# PRN_S2_v1_0.net
KiCad netlist of a schematic drawn in EAGLE
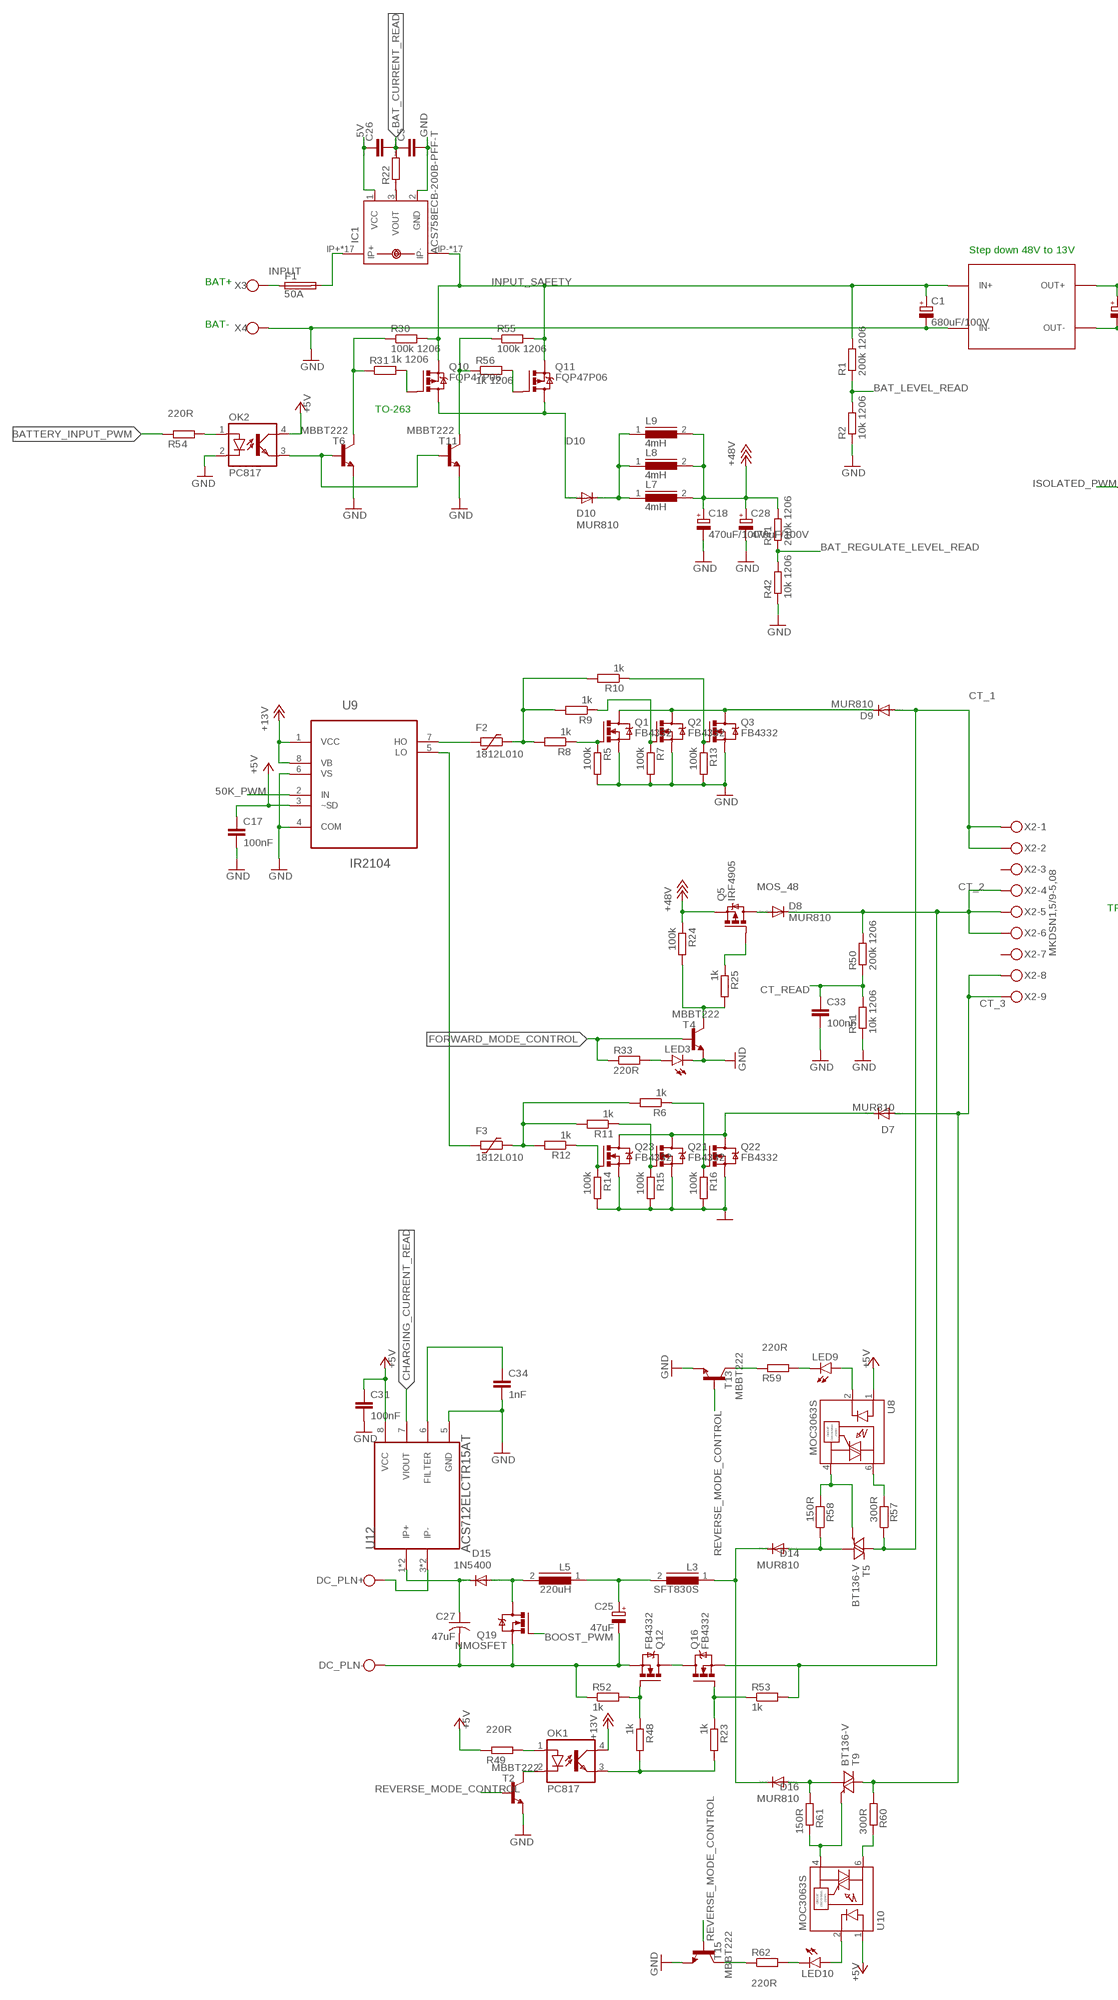
[diagram p0: schematic, sheet 1, part 1 of 2]
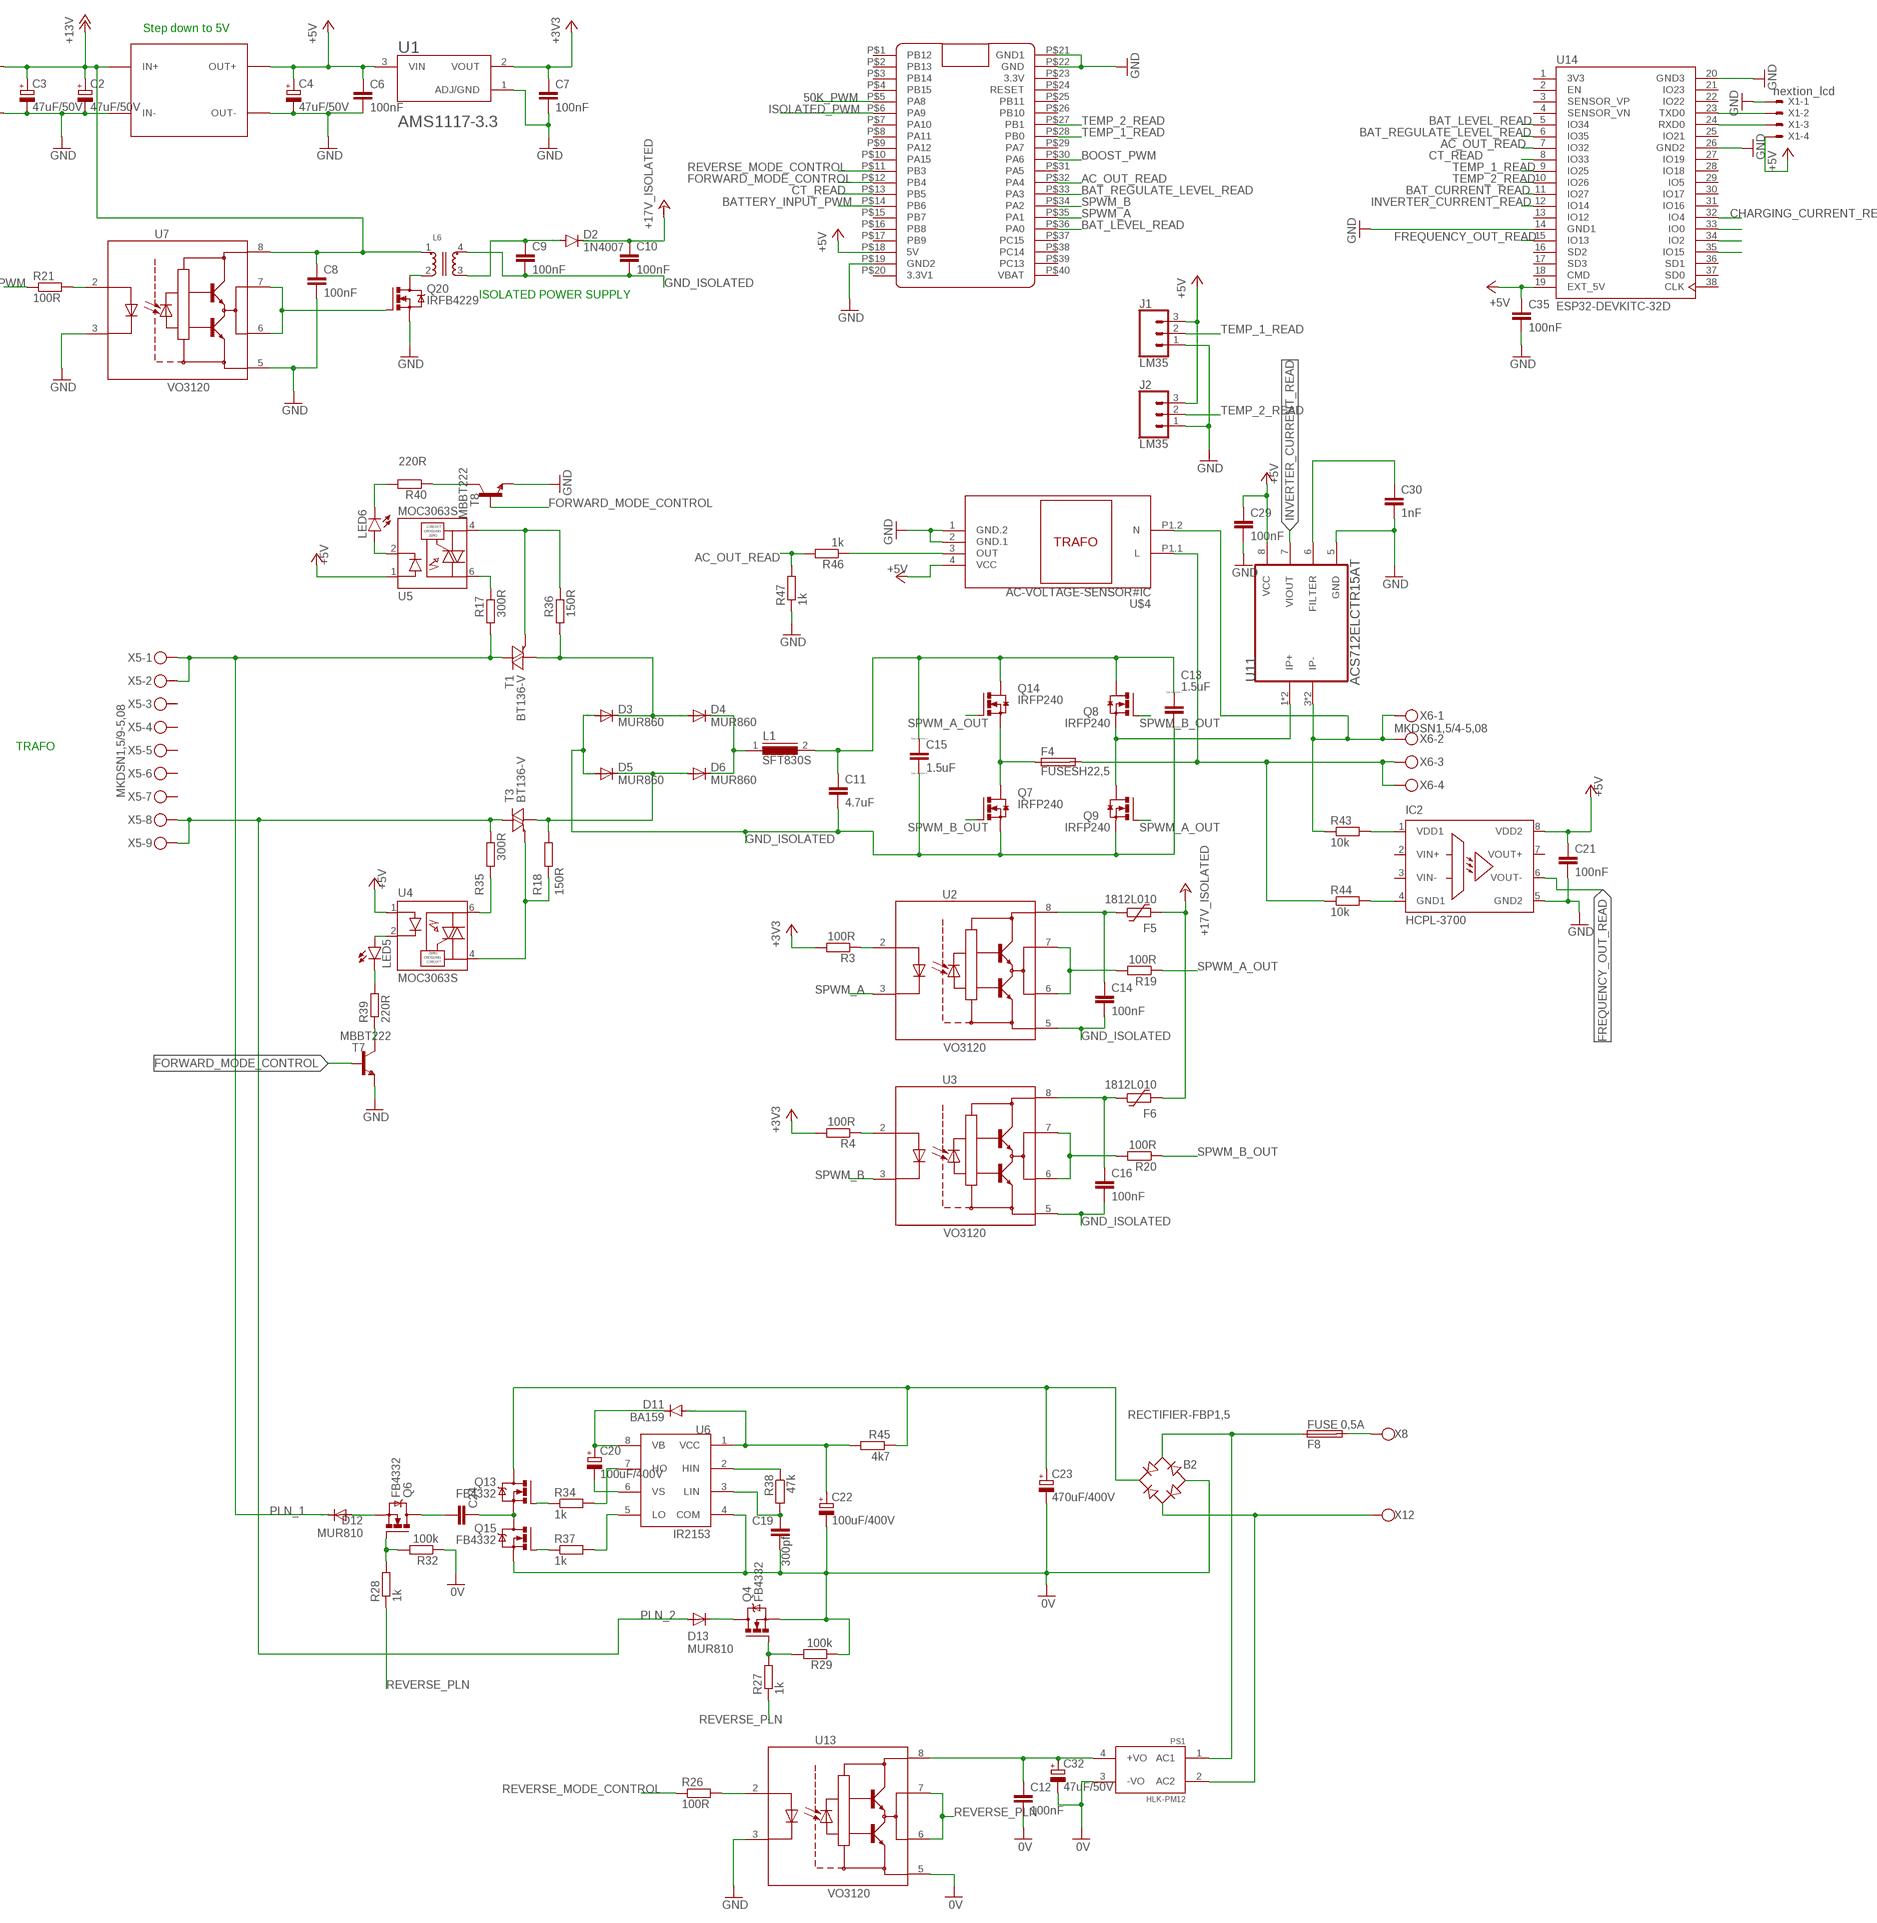
[diagram p1: schematic, sheet 1, part 2 of 2]

(export (version "E")
  (design (tool "Eeschema 10.0.6"))
  (components
    (comp (ref "B2")
      (value "RECTIFIER-FBP1,5")
      (footprint "eagle-import:FBP1,5")
      (libsource (lib "eagle-import") (part "RECTIFIER-FBP1,5"))
    )
    (comp (ref "C1")
      (value "680uF/100V")
      (footprint "eagle-import:E7,5-18")
      (libsource (lib "eagle-import") (part "CPOL-EUE7.5-18"))
    )
    (comp (ref "C2")
      (value "47uF/50V")
      (footprint "eagle-import:E2,5-6")
      (libsource (lib "eagle-import") (part "rcl_334_CPOL-EUE2.5-6"))
    )
    (comp (ref "C3")
      (value "47uF/50V")
      (footprint "eagle-import:E2,5-6")
      (libsource (lib "eagle-import") (part "rcl_334_CPOL-EUE2.5-6"))
    )
    (comp (ref "C4")
      (value "47uF/50V")
      (footprint "eagle-import:E2,5-6")
      (libsource (lib "eagle-import") (part "rcl_334_CPOL-EUE2.5-6"))
    )
    (comp (ref "C5")
      (value "CC0603")
      (footprint "eagle-import:C0603")
      (libsource (lib "eagle-import") (part "CC0603"))
    )
    (comp (ref "C6")
      (value "100nF")
      (footprint "eagle-import:C0805K")
      (libsource (lib "eagle-import") (part "rcl_334_C-EUC0805K"))
    )
    (comp (ref "C7")
      (value "100nF")
      (footprint "eagle-import:C0805K")
      (libsource (lib "eagle-import") (part "rcl_334_C-EUC0805K"))
    )
    (comp (ref "C8")
      (value "100nF")
      (footprint "eagle-import:C050-025X075")
      (libsource (lib "eagle-import") (part "rcl_334_C-EU050-025X075"))
    )
    (comp (ref "C9")
      (value "100nF")
      (footprint "eagle-import:C050-025X075")
      (libsource (lib "eagle-import") (part "rcl_334_C-EU050-025X075"))
    )
    (comp (ref "C10")
      (value "100nF")
      (footprint "eagle-import:C050-025X075")
      (libsource (lib "eagle-import") (part "rcl_334_C-EU050-025X075"))
    )
    (comp (ref "C11")
      (value "4.7uF")
      (footprint "eagle-import:C275-113X316")
      (libsource (lib "eagle-import") (part "C-EU275-113X316"))
    )
    (comp (ref "C12")
      (value "100nF")
      (footprint "eagle-import:C050-025X075")
      (libsource (lib "eagle-import") (part "rcl_334_C-EU050-025X075"))
    )
    (comp (ref "C13")
      (value "1.5uF")
      (footprint "eagle-import:C150-091X182")
      (libsource (lib "eagle-import") (part "resistor_C-EU150-091X182"))
    )
    (comp (ref "C14")
      (value "100nF")
      (footprint "eagle-import:C0805K")
      (libsource (lib "eagle-import") (part "rcl_334_C-EUC0805K"))
    )
    (comp (ref "C15")
      (value "1.5uF")
      (footprint "eagle-import:C150-091X182")
      (libsource (lib "eagle-import") (part "resistor_C-EU150-091X182"))
    )
    (comp (ref "C16")
      (value "100nF")
      (footprint "eagle-import:C0805K")
      (libsource (lib "eagle-import") (part "rcl_334_C-EUC0805K"))
    )
    (comp (ref "C17")
      (value "100nF")
      (footprint "eagle-import:C0805K")
      (libsource (lib "eagle-import") (part "rcl_334_C-EUC0805K"))
    )
    (comp (ref "C18")
      (value "470uF/100V")
      (footprint "eagle-import:E7,5-18")
      (libsource (lib "eagle-import") (part "CPOL-EUE7.5-18"))
    )
    (comp (ref "C19")
      (value "300pf")
      (footprint "eagle-import:C0805")
      (libsource (lib "eagle-import") (part "rcl@1_C-EUC0805"))
    )
    (comp (ref "C20")
      (value "100uF/400V")
      (footprint "eagle-import:E7,5-18")
      (libsource (lib "eagle-import") (part "rcl_334_CPOL-EUE7.5-18"))
    )
    (comp (ref "C21")
      (value "100nF")
      (footprint "eagle-import:C0805K")
      (libsource (lib "eagle-import") (part "rcl_334_C-EUC0805K"))
    )
    (comp (ref "C22")
      (value "100uF/400V")
      (footprint "eagle-import:E7,5-18")
      (libsource (lib "eagle-import") (part "rcl_334_CPOL-EUE7.5-18"))
    )
    (comp (ref "C23")
      (value "470uF/400V")
      (footprint "eagle-import:EB35D")
      (libsource (lib "eagle-import") (part "rcl_334_CPOL-EUE10-35"))
    )
    (comp (ref "C24")
      (value "C-EU325-137X374")
      (footprint "eagle-import:C325-137X374")
      (libsource (lib "eagle-import") (part "rcl@1_C-EU325-137X374"))
    )
    (comp (ref "C25")
      (value "47uF")
      (footprint "eagle-import:E7,5-18")
      (libsource (lib "eagle-import") (part "rcl@1_CPOL-EUE7.5-18"))
    )
    (comp (ref "C26")
      (value "CC0603")
      (footprint "eagle-import:C0603")
      (libsource (lib "eagle-import") (part "CC0603"))
    )
    (comp (ref "C27")
      (value "47uF")
      (footprint "eagle-import:C050-050X075")
      (libsource (lib "eagle-import") (part "C-US050-050X075"))
    )
    (comp (ref "C28")
      (value "470uF/100V")
      (footprint "eagle-import:E7,5-18")
      (libsource (lib "eagle-import") (part "CPOL-EUE7.5-18"))
    )
    (comp (ref "C29")
      (value "100nF")
      (footprint "eagle-import:C0805K")
      (libsource (lib "eagle-import") (part "rcl_334_C-EUC0805K"))
    )
    (comp (ref "C30")
      (value "1nF")
      (footprint "eagle-import:C0805K")
      (libsource (lib "eagle-import") (part "rcl_334_C-EUC0805K"))
    )
    (comp (ref "C31")
      (value "100nF")
      (footprint "eagle-import:C0805K")
      (libsource (lib "eagle-import") (part "rcl_334_C-EUC0805K"))
    )
    (comp (ref "C32")
      (value "47uF/50V")
      (footprint "eagle-import:E2,5-6")
      (libsource (lib "eagle-import") (part "rcl_334_CPOL-EUE2.5-6"))
    )
    (comp (ref "C33")
      (value "100nF")
      (footprint "eagle-import:C050-025X075")
      (libsource (lib "eagle-import") (part "rcl_334_C-EU050-025X075"))
    )
    (comp (ref "C34")
      (value "1nF")
      (footprint "eagle-import:C0805K")
      (libsource (lib "eagle-import") (part "rcl_334_C-EUC0805K"))
    )
    (comp (ref "C35")
      (value "100nF")
      (footprint "eagle-import:C0805K")
      (libsource (lib "eagle-import") (part "rcl_334_C-EUC0805K"))
    )
    (comp (ref "D2")
      (value "1N4007")
      (footprint "eagle-import:DO41-10")
      (libsource (lib "eagle-import") (part "diode_210_1N4004"))
    )
    (comp (ref "D3")
      (value "MUR860")
      (footprint "eagle-import:TO220ACS")
      (libsource (lib "eagle-import") (part "MUR810"))
    )
    (comp (ref "D4")
      (value "MUR860")
      (footprint "eagle-import:TO220ACS")
      (libsource (lib "eagle-import") (part "MUR810"))
    )
    (comp (ref "D5")
      (value "MUR860")
      (footprint "eagle-import:TO220ACS")
      (libsource (lib "eagle-import") (part "MUR810"))
    )
    (comp (ref "D6")
      (value "MUR860")
      (footprint "eagle-import:TO220ACS")
      (libsource (lib "eagle-import") (part "MUR810"))
    )
    (comp (ref "D7")
      (value "MUR810")
      (footprint "eagle-import:TO220ACS")
      (libsource (lib "eagle-import") (part "MUR810"))
    )
    (comp (ref "D8")
      (value "MUR810")
      (footprint "eagle-import:TO220ACS")
      (libsource (lib "eagle-import") (part "MUR810"))
    )
    (comp (ref "D9")
      (value "MUR810")
      (footprint "eagle-import:TO220ACS")
      (libsource (lib "eagle-import") (part "MUR810"))
    )
    (comp (ref "D10")
      (value "MUR810")
      (footprint "eagle-import:TO220ACS")
      (libsource (lib "eagle-import") (part "MUR810"))
    )
    (comp (ref "D11")
      (value "BA159")
      (footprint "eagle-import:DO41-10")
      (libsource (lib "eagle-import") (part "1N4004"))
    )
    (comp (ref "D12")
      (value "MUR810")
      (footprint "eagle-import:TO220ACS")
      (libsource (lib "eagle-import") (part "MUR810"))
    )
    (comp (ref "D13")
      (value "MUR810")
      (footprint "eagle-import:TO220ACS")
      (libsource (lib "eagle-import") (part "MUR810"))
    )
    (comp (ref "D14")
      (value "MUR810")
      (footprint "eagle-import:TO220ACS")
      (libsource (lib "eagle-import") (part "MUR810"))
    )
    (comp (ref "D15")
      (value "1N5400")
      (footprint "eagle-import:DO201-15")
      (libsource (lib "eagle-import") (part "1N5400"))
    )
    (comp (ref "D16")
      (value "MUR810")
      (footprint "eagle-import:TO220ACS")
      (libsource (lib "eagle-import") (part "MUR810"))
    )
    (comp (ref "DC_PLN+")
      (value "W237-112")
      (footprint "eagle-import:W237-112")
      (fields (field (name "MPN") "237-112"))
      (libsource (lib "eagle-import") (part "W237-112"))
    )
    (comp (ref "DC_PLN-")
      (value "W237-112")
      (footprint "eagle-import:W237-112")
      (fields (field (name "MPN") "237-112"))
      (libsource (lib "eagle-import") (part "W237-112"))
    )
    (comp (ref "F1")
      (value "50A")
      (footprint "eagle-import:GSH15")
      (fields (field (name "MPN") "64900001039"))
      (libsource (lib "eagle-import") (part "GSH15"))
    )
    (comp (ref "F2")
      (value "1812L010")
      (footprint "eagle-import:1812L")
      (fields (field (name "MF") "Littelfuse"))
      (libsource (lib "eagle-import") (part "?1812L010"))
    )
    (comp (ref "F3")
      (value "1812L010")
      (footprint "eagle-import:1812L")
      (fields (field (name "MF") "Littelfuse"))
      (libsource (lib "eagle-import") (part "?1812L010"))
    )
    (comp (ref "F4")
      (value "FUSESH22,5")
      (footprint "eagle-import:SH22,5")
      (libsource (lib "eagle-import") (part "FUSESH22,5"))
    )
    (comp (ref "F5")
      (value "1812L010")
      (footprint "eagle-import:1812L")
      (fields (field (name "MF") "Littelfuse"))
      (libsource (lib "eagle-import") (part "?1812L010"))
    )
    (comp (ref "F6")
      (value "1812L010")
      (footprint "eagle-import:1812L")
      (fields (field (name "MF") "Littelfuse"))
      (libsource (lib "eagle-import") (part "?1812L010"))
    )
    (comp (ref "F8")
      (value "FUSE 0,5A")
      (footprint "eagle-import:SH22,5")
      (libsource (lib "eagle-import") (part "FUSESH22,5"))
    )
    (comp (ref "IC1")
      (value "ACS758ECB-200B-PFF-T")
      (footprint "eagle-import:CB-PFF")
      (libsource (lib "eagle-import") (part "ACS758ECB-200B-PFF-T"))
    )
    (comp (ref "IC2")
      (value "HCPL-3700")
      (footprint "eagle-import:DIL08")
      (fields (field (name "MF") "ON") (field (name "MP") "HCPL3700"))
      (libsource (lib "eagle-import") (part "HCPL-3700"))
    )
    (comp (ref "J1")
      (value "LM35")
      (footprint "eagle-import:1X03")
      (libsource (lib "eagle-import") (part "CONN_03"))
    )
    (comp (ref "J2")
      (value "LM35")
      (footprint "eagle-import:1X03")
      (libsource (lib "eagle-import") (part "CONN_03"))
    )
    (comp (ref "L1")
      (value "SFT830S")
      (footprint "eagle-import:SFT830S")
      (libsource (lib "eagle-import") (part "SFT830S"))
    )
    (comp (ref "L3")
      (value "SFT830S")
      (footprint "eagle-import:SFT830S")
      (libsource (lib "eagle-import") (part "SFT830S"))
    )
    (comp (ref "L5")
      (value "220uH")
      (footprint "eagle-import:SFT830S")
      (libsource (lib "eagle-import") (part "SFT830S"))
    )
    (comp (ref "L6")
      (value "WE-AMT_750082107")
      (footprint "eagle-import:WE-AMT_750082107")
      (libsource (lib "eagle-import") (part "WE-AMT_750082107"))
    )
    (comp (ref "L7")
      (value "4mH")
      (footprint "eagle-import:SFT830S")
      (libsource (lib "eagle-import") (part "SFT830S"))
    )
    (comp (ref "L8")
      (value "4mH")
      (footprint "eagle-import:SFT830S")
      (libsource (lib "eagle-import") (part "SFT830S"))
    )
    (comp (ref "L9")
      (value "4mH")
      (footprint "eagle-import:SFT830S")
      (libsource (lib "eagle-import") (part "SFT830S"))
    )
    (comp (ref "LED3")
      (value "LEDCHIPLED_0805")
      (footprint "eagle-import:CHIPLED_0805")
      (libsource (lib "eagle-import") (part "LEDCHIPLED_0805"))
    )
    (comp (ref "LED5")
      (value "LEDCHIPLED_0805")
      (footprint "eagle-import:CHIPLED_0805")
      (libsource (lib "eagle-import") (part "LEDCHIPLED_0805"))
    )
    (comp (ref "LED6")
      (value "LEDCHIPLED_0805")
      (footprint "eagle-import:CHIPLED_0805")
      (libsource (lib "eagle-import") (part "LEDCHIPLED_0805"))
    )
    (comp (ref "LED9")
      (value "LEDCHIPLED_0805")
      (footprint "eagle-import:CHIPLED_0805")
      (libsource (lib "eagle-import") (part "LEDCHIPLED_0805"))
    )
    (comp (ref "LED10")
      (value "LEDCHIPLED_0805")
      (footprint "eagle-import:CHIPLED_0805")
      (libsource (lib "eagle-import") (part "LEDCHIPLED_0805"))
    )
    (comp (ref "OK1")
      (value "PC817")
      (footprint "eagle-import:DIL04")
      (fields (field (name "MPN") "PC817X4J000F"))
      (libsource (lib "eagle-import") (part "PC817"))
    )
    (comp (ref "OK2")
      (value "PC817")
      (footprint "eagle-import:DIL04")
      (fields (field (name "MPN") "PC817X4J000F"))
      (libsource (lib "eagle-import") (part "PC817"))
    )
    (comp (ref "PS1")
      (value "HLK-PM12")
      (footprint "eagle-import:CONV_HLK-PM03")
      (fields (field (name "MF") "Hi-link") (field (name "MP") "HLK-PM03"))
      (libsource (lib "eagle-import") (part "HLK-PM03"))
    )
    (comp (ref "Q1")
      (value "FB4332")
      (footprint "eagle-import:TO220BV")
      (libsource (lib "eagle-import") (part "NMOSFETTO220_"))
    )
    (comp (ref "Q2")
      (value "FB4332")
      (footprint "eagle-import:TO220BV")
      (libsource (lib "eagle-import") (part "NMOSFETTO220_"))
    )
    (comp (ref "Q3")
      (value "FB4332")
      (footprint "eagle-import:TO220BV")
      (libsource (lib "eagle-import") (part "NMOSFETTO220_"))
    )
    (comp (ref "Q4")
      (value "FB4332")
      (footprint "eagle-import:TO220BV")
      (libsource (lib "eagle-import") (part "NMOSFETTO220_"))
    )
    (comp (ref "Q5")
      (value "IRF4905")
      (footprint "eagle-import:TO220BV")
      (libsource (lib "eagle-import") (part "IRF9530"))
    )
    (comp (ref "Q6")
      (value "FB4332")
      (footprint "eagle-import:TO220BV")
      (libsource (lib "eagle-import") (part "NMOSFETTO220_"))
    )
    (comp (ref "Q7")
      (value "IRFP240")
      (footprint "eagle-import:TO247BV")
      (libsource (lib "eagle-import") (part "IRFP240"))
    )
    (comp (ref "Q8")
      (value "IRFP240")
      (footprint "eagle-import:TO247BV")
      (libsource (lib "eagle-import") (part "IRFP240"))
    )
    (comp (ref "Q9")
      (value "IRFP240")
      (footprint "eagle-import:TO247BV")
      (libsource (lib "eagle-import") (part "IRFP240"))
    )
    (comp (ref "Q10")
      (value "FQP47P06")
      (footprint "eagle-import:TO220BV")
      (libsource (lib "eagle-import") (part "IRF9530"))
    )
    (comp (ref "Q11")
      (value "FQP47P06")
      (footprint "eagle-import:TO220BV")
      (libsource (lib "eagle-import") (part "IRF9530"))
    )
    (comp (ref "Q12")
      (value "FB4332")
      (footprint "eagle-import:TO220BV")
      (libsource (lib "eagle-import") (part "NMOSFETTO220_"))
    )
    (comp (ref "Q13")
      (value "FB4332")
      (footprint "eagle-import:TO220BV")
      (libsource (lib "eagle-import") (part "NMOSFETTO220_"))
    )
    (comp (ref "Q14")
      (value "IRFP240")
      (footprint "eagle-import:TO247BV")
      (libsource (lib "eagle-import") (part "IRFP240"))
    )
    (comp (ref "Q15")
      (value "FB4332")
      (footprint "eagle-import:TO220BV")
      (libsource (lib "eagle-import") (part "NMOSFETTO220_"))
    )
    (comp (ref "Q16")
      (value "FB4332")
      (footprint "eagle-import:TO220BV")
      (libsource (lib "eagle-import") (part "NMOSFETTO220_"))
    )
    (comp (ref "Q19")
      (value "NMOSFET")
      (footprint "eagle-import:TO220BV")
      (libsource (lib "eagle-import") (part "NMOSFETTO220_"))
    )
    (comp (ref "Q20")
      (value "IRFB4229")
      (footprint "eagle-import:TO220BV")
      (libsource (lib "eagle-import") (part "NMOSFETTO220_"))
    )
    (comp (ref "Q21")
      (value "FB4332")
      (footprint "eagle-import:TO220BV")
      (libsource (lib "eagle-import") (part "NMOSFETTO220_"))
    )
    (comp (ref "Q22")
      (value "FB4332")
      (footprint "eagle-import:TO220BV")
      (libsource (lib "eagle-import") (part "NMOSFETTO220_"))
    )
    (comp (ref "Q23")
      (value "FB4332")
      (footprint "eagle-import:TO220BV")
      (libsource (lib "eagle-import") (part "NMOSFETTO220_"))
    )
    (comp (ref "R1")
      (value "200k 1206")
      (footprint "eagle-import:R1206")
      (libsource (lib "eagle-import") (part "rcl_334_R-EU_R1206"))
    )
    (comp (ref "R2")
      (value "10k 1206")
      (footprint "eagle-import:R1206")
      (libsource (lib "eagle-import") (part "rcl_334_R-EU_R1206"))
    )
    (comp (ref "R3")
      (value "100R")
      (footprint "eagle-import:R0805")
      (libsource (lib "eagle-import") (part "rcl_334_R-EU_R0805"))
    )
    (comp (ref "R4")
      (value "100R")
      (footprint "eagle-import:R0805")
      (libsource (lib "eagle-import") (part "rcl_334_R-EU_R0805"))
    )
    (comp (ref "R5")
      (value "100k")
      (footprint "eagle-import:R0805")
      (libsource (lib "eagle-import") (part "rcl_334_R-EU_R0805"))
    )
    (comp (ref "R6")
      (value "1k")
      (footprint "eagle-import:R0805")
      (libsource (lib "eagle-import") (part "rcl_334_R-EU_R0805"))
    )
    (comp (ref "R7")
      (value "100k")
      (footprint "eagle-import:R0805")
      (libsource (lib "eagle-import") (part "rcl_334_R-EU_R0805"))
    )
    (comp (ref "R8")
      (value "1k")
      (footprint "eagle-import:R0805")
      (libsource (lib "eagle-import") (part "rcl_334_R-EU_R0805"))
    )
    (comp (ref "R9")
      (value "1k")
      (footprint "eagle-import:R0805")
      (libsource (lib "eagle-import") (part "rcl_334_R-EU_R0805"))
    )
    (comp (ref "R10")
      (value "1k")
      (footprint "eagle-import:R0805")
      (libsource (lib "eagle-import") (part "rcl_334_R-EU_R0805"))
    )
    (comp (ref "R11")
      (value "1k")
      (footprint "eagle-import:R0805")
      (libsource (lib "eagle-import") (part "rcl_334_R-EU_R0805"))
    )
    (comp (ref "R12")
      (value "1k")
      (footprint "eagle-import:R0805")
      (libsource (lib "eagle-import") (part "rcl_334_R-EU_R0805"))
    )
    (comp (ref "R13")
      (value "100k")
      (footprint "eagle-import:R0805")
      (libsource (lib "eagle-import") (part "rcl_334_R-EU_R0805"))
    )
    (comp (ref "R14")
      (value "100k")
      (footprint "eagle-import:R0805")
      (libsource (lib "eagle-import") (part "rcl_334_R-EU_R0805"))
    )
    (comp (ref "R15")
      (value "100k")
      (footprint "eagle-import:R0805")
      (libsource (lib "eagle-import") (part "rcl_334_R-EU_R0805"))
    )
    (comp (ref "R16")
      (value "100k")
      (footprint "eagle-import:R0805")
      (libsource (lib "eagle-import") (part "rcl_334_R-EU_R0805"))
    )
    (comp (ref "R17")
      (value "300R")
      (footprint "eagle-import:0207_15")
      (libsource (lib "eagle-import") (part "rcl_334_R-EU_0207/15"))
    )
    (comp (ref "R18")
      (value "150R")
      (footprint "eagle-import:0207_15")
      (libsource (lib "eagle-import") (part "rcl_334_R-EU_0207/15"))
    )
    (comp (ref "R19")
      (value "100R")
      (footprint "eagle-import:R0805")
      (libsource (lib "eagle-import") (part "rcl_334_R-EU_R0805"))
    )
    (comp (ref "R20")
      (value "100R")
      (footprint "eagle-import:R0805")
      (libsource (lib "eagle-import") (part "rcl_334_R-EU_R0805"))
    )
    (comp (ref "R21")
      (value "100R")
      (footprint "eagle-import:R0805")
      (libsource (lib "eagle-import") (part "rcl_334_R-EU_R0805"))
    )
    (comp (ref "R22")
      (value "RR0603")
      (footprint "eagle-import:R0603")
      (libsource (lib "eagle-import") (part "RR0603"))
    )
    (comp (ref "R23")
      (value "1k")
      (footprint "eagle-import:R0805")
      (libsource (lib "eagle-import") (part "rcl_334_R-EU_R0805"))
    )
    (comp (ref "R24")
      (value "100k")
      (footprint "eagle-import:R0805")
      (libsource (lib "eagle-import") (part "rcl_334_R-EU_R0805"))
    )
    (comp (ref "R25")
      (value "1k")
      (footprint "eagle-import:R0805")
      (libsource (lib "eagle-import") (part "rcl_334_R-EU_R0805"))
    )
    (comp (ref "R26")
      (value "100R")
      (footprint "eagle-import:R0805")
      (libsource (lib "eagle-import") (part "rcl_334_R-EU_R0805"))
    )
    (comp (ref "R27")
      (value "1k")
      (footprint "eagle-import:R0805")
      (libsource (lib "eagle-import") (part "rcl_334_R-EU_R0805"))
    )
    (comp (ref "R28")
      (value "1k")
      (footprint "eagle-import:R0805")
      (libsource (lib "eagle-import") (part "rcl_334_R-EU_R0805"))
    )
    (comp (ref "R29")
      (value "100k")
      (footprint "eagle-import:R0805")
      (libsource (lib "eagle-import") (part "rcl_334_R-EU_R0805"))
    )
    (comp (ref "R30")
      (value "100k 1206")
      (footprint "eagle-import:R1206")
      (libsource (lib "eagle-import") (part "rcl_334_R-EU_R1206"))
    )
    (comp (ref "R31")
      (value "1k 1206")
      (footprint "eagle-import:R1206")
      (libsource (lib "eagle-import") (part "rcl_334_R-EU_R1206"))
    )
    (comp (ref "R32")
      (value "100k")
      (footprint "eagle-import:R0805")
      (libsource (lib "eagle-import") (part "rcl_334_R-EU_R0805"))
    )
    (comp (ref "R33")
      (value "220R")
      (footprint "eagle-import:R0805")
      (libsource (lib "eagle-import") (part "rcl_334_R-EU_R0805"))
    )
    (comp (ref "R34")
      (value "1k")
      (footprint "eagle-import:0207_12")
      (libsource (lib "eagle-import") (part "rcl_334_R-EU_0207/12"))
    )
    (comp (ref "R35")
      (value "300R")
      (footprint "eagle-import:0207_15")
      (libsource (lib "eagle-import") (part "rcl_334_R-EU_0207/15"))
    )
    (comp (ref "R36")
      (value "150R")
      (footprint "eagle-import:0207_15")
      (libsource (lib "eagle-import") (part "rcl_334_R-EU_0207/15"))
    )
    (comp (ref "R37")
      (value "1k")
      (footprint "eagle-import:0207_12")
      (libsource (lib "eagle-import") (part "rcl_334_R-EU_0207/12"))
    )
    (comp (ref "R38")
      (value "47k")
      (footprint "eagle-import:0617_17")
      (libsource (lib "eagle-import") (part "R-EU_0617/17"))
    )
    (comp (ref "R39")
      (value "220R")
      (footprint "eagle-import:R0805")
      (libsource (lib "eagle-import") (part "rcl_334_R-EU_R0805"))
    )
    (comp (ref "R40")
      (value "220R")
      (footprint "eagle-import:R0805")
      (libsource (lib "eagle-import") (part "rcl_334_R-EU_R0805"))
    )
    (comp (ref "R41")
      (value "200k 1206")
      (footprint "eagle-import:R1206")
      (libsource (lib "eagle-import") (part "rcl_334_R-EU_R1206"))
    )
    (comp (ref "R42")
      (value "10k 1206")
      (footprint "eagle-import:R1206")
      (libsource (lib "eagle-import") (part "rcl_334_R-EU_R1206"))
    )
    (comp (ref "R43")
      (value "10k")
      (footprint "eagle-import:0207_12")
      (libsource (lib "eagle-import") (part "rcl_334_R-EU_0207/12"))
    )
    (comp (ref "R44")
      (value "10k")
      (footprint "eagle-import:0207_12")
      (libsource (lib "eagle-import") (part "rcl_334_R-EU_0207/12"))
    )
    (comp (ref "R45")
      (value "4k7")
      (footprint "eagle-import:0617_17")
      (libsource (lib "eagle-import") (part "R-EU_0617/17"))
    )
    (comp (ref "R46")
      (value "1k")
      (footprint "eagle-import:R1206")
      (libsource (lib "eagle-import") (part "rcl_334_R-EU_R1206"))
    )
    (comp (ref "R47")
      (value "1k")
      (footprint "eagle-import:R1206")
      (libsource (lib "eagle-import") (part "rcl_334_R-EU_R1206"))
    )
    (comp (ref "R48")
      (value "1k")
      (footprint "eagle-import:R0805")
      (libsource (lib "eagle-import") (part "rcl_334_R-EU_R0805"))
    )
    (comp (ref "R49")
      (value "220R")
      (footprint "eagle-import:R0805")
      (libsource (lib "eagle-import") (part "rcl_334_R-EU_R0805"))
    )
    (comp (ref "R50")
      (value "200k 1206")
      (footprint "eagle-import:R1206")
      (libsource (lib "eagle-import") (part "rcl_334_R-EU_R1206"))
    )
    (comp (ref "R51")
      (value "10k 1206")
      (footprint "eagle-import:R1206")
      (libsource (lib "eagle-import") (part "rcl_334_R-EU_R1206"))
    )
    (comp (ref "R52")
      (value "1k")
      (footprint "eagle-import:R0805")
      (libsource (lib "eagle-import") (part "rcl_334_R-EU_R0805"))
    )
    (comp (ref "R53")
      (value "1k")
      (footprint "eagle-import:R0805")
      (libsource (lib "eagle-import") (part "rcl_334_R-EU_R0805"))
    )
    (comp (ref "R54")
      (value "220R")
      (footprint "eagle-import:R0805")
      (libsource (lib "eagle-import") (part "rcl_334_R-EU_R0805"))
    )
    (comp (ref "R55")
      (value "100k 1206")
      (footprint "eagle-import:R1206")
      (libsource (lib "eagle-import") (part "rcl_334_R-EU_R1206"))
    )
    (comp (ref "R56")
      (value "1k 1206")
      (footprint "eagle-import:R1206")
      (libsource (lib "eagle-import") (part "rcl_334_R-EU_R1206"))
    )
    (comp (ref "R57")
      (value "300R")
      (footprint "eagle-import:0207_15")
      (libsource (lib "eagle-import") (part "rcl_334_R-EU_0207/15"))
    )
    (comp (ref "R58")
      (value "150R")
      (footprint "eagle-import:0207_15")
      (libsource (lib "eagle-import") (part "rcl_334_R-EU_0207/15"))
    )
    (comp (ref "R59")
      (value "220R")
      (footprint "eagle-import:R0805")
      (libsource (lib "eagle-import") (part "rcl_334_R-EU_R0805"))
    )
    (comp (ref "R60")
      (value "300R")
      (footprint "eagle-import:0207_15")
      (libsource (lib "eagle-import") (part "rcl_334_R-EU_0207/15"))
    )
    (comp (ref "R61")
      (value "150R")
      (footprint "eagle-import:0207_15")
      (libsource (lib "eagle-import") (part "rcl_334_R-EU_0207/15"))
    )
    (comp (ref "R62")
      (value "220R")
      (footprint "eagle-import:R0805")
      (libsource (lib "eagle-import") (part "rcl_334_R-EU_R0805"))
    )
    (comp (ref "T1")
      (value "BT136-V")
      (footprint "eagle-import:TO220BV")
      (libsource (lib "eagle-import") (part "BT138-V"))
    )
    (comp (ref "T2")
      (value "MBBT222")
      (footprint "eagle-import:SOT23-EBC")
      (libsource (lib "eagle-import") (part "-NPN-SOT23-EBC"))
    )
    (comp (ref "T3")
      (value "BT136-V")
      (footprint "eagle-import:TO220BV")
      (libsource (lib "eagle-import") (part "BT138-V"))
    )
    (comp (ref "T4")
      (value "MBBT222")
      (footprint "eagle-import:SOT23-EBC")
      (libsource (lib "eagle-import") (part "-NPN-SOT23-EBC"))
    )
    (comp (ref "T5")
      (value "BT136-V")
      (footprint "eagle-import:TO220BV")
      (libsource (lib "eagle-import") (part "BT138-V"))
    )
    (comp (ref "T6")
      (value "MBBT222")
      (footprint "eagle-import:SOT23-EBC")
      (libsource (lib "eagle-import") (part "-NPN-SOT23-EBC"))
    )
    (comp (ref "T7")
      (value "MBBT222")
      (footprint "eagle-import:SOT23-EBC")
      (libsource (lib "eagle-import") (part "-NPN-SOT23-EBC"))
    )
    (comp (ref "T8")
      (value "MBBT222")
      (footprint "eagle-import:SOT23-EBC")
      (libsource (lib "eagle-import") (part "-NPN-SOT23-EBC"))
    )
    (comp (ref "T9")
      (value "BT136-V")
      (footprint "eagle-import:TO220BV")
      (libsource (lib "eagle-import") (part "BT138-V"))
    )
    (comp (ref "T11")
      (value "MBBT222")
      (footprint "eagle-import:SOT23-EBC")
      (libsource (lib "eagle-import") (part "-NPN-SOT23-EBC"))
    )
    (comp (ref "T13")
      (value "MBBT222")
      (footprint "eagle-import:SOT23-EBC")
      (libsource (lib "eagle-import") (part "-NPN-SOT23-EBC"))
    )
    (comp (ref "T15")
      (value "MBBT222")
      (footprint "eagle-import:SOT23-EBC")
      (libsource (lib "eagle-import") (part "-NPN-SOT23-EBC"))
    )
    (comp (ref "U$1")
      (value "DC-DC-STEP-DOWN-LM2596")
      (footprint "eagle-import:DC-DC-STEP-DOWN-LM2596")
      (libsource (lib "eagle-import") (part "DC-DC-STEP-DOWN-LM2596"))
    )
    (comp (ref "U$2")
      (value "DC-DC-STEP-DOWN-LM2596")
      (footprint "eagle-import:DC-DC-STEP-DOWN-LM2596")
      (libsource (lib "eagle-import") (part "DC-DC-STEP-DOWN-LM2596"))
    )
    (comp (ref "U$3")
      (value "BLUE_PILL")
      (footprint "eagle-import:BLUE_PILL")
      (libsource (lib "eagle-import") (part "BLUE_PILL"))
    )
    (comp (ref "U$4")
      (value "AC-VOLTAGE-SENSOR#IC")
      (footprint "eagle-import:AC-VOLTAGE-SENSOR#IC")
      (libsource (lib "eagle-import") (part "AC-VOLTAGE-SENSOR#IC"))
    )
    (comp (ref "U1")
      (value "AMS1117-3.3")
      (footprint "eagle-import:SOT229P700X180-4N")
      (fields (field (name "MF") "ams"))
      (libsource (lib "eagle-import") (part "AMS1117-3.3"))
    )
    (comp (ref "U2")
      (value "VO3120")
      (footprint "eagle-import:DIP762W50P254L977H451Q8")
      (fields (field (name "MF") "Vishay Semiconductor"))
      (libsource (lib "eagle-import") (part "VO3120"))
    )
    (comp (ref "U3")
      (value "VO3120")
      (footprint "eagle-import:DIP762W50P254L977H451Q8")
      (fields (field (name "MF") "Vishay Semiconductor"))
      (libsource (lib "eagle-import") (part "VO3120"))
    )
    (comp (ref "U4")
      (value "MOC3063S")
      (footprint "eagle-import:DIP762W50P254L730H500Q6")
      (fields (field (name "MF") "Lite-On Inc.") (field (name "MP") "MOC3063"))
      (libsource (lib "eagle-import") (part "MOC3063S"))
    )
    (comp (ref "U5")
      (value "MOC3063S")
      (footprint "eagle-import:DIP762W50P254L730H500Q6")
      (fields (field (name "MF") "Lite-On Inc.") (field (name "MP") "MOC3063"))
      (libsource (lib "eagle-import") (part "MOC3063S"))
    )
    (comp (ref "U6")
      (value "IR2153")
      (footprint "eagle-import:DIL08")
      (libsource (lib "eagle-import") (part "IR2101"))
    )
    (comp (ref "U7")
      (value "VO3120")
      (footprint "eagle-import:DIP762W50P254L977H451Q8")
      (fields (field (name "MF") "Vishay Semiconductor"))
      (libsource (lib "eagle-import") (part "VO3120"))
    )
    (comp (ref "U8")
      (value "MOC3063S")
      (footprint "eagle-import:DIP762W50P254L730H500Q6")
      (fields (field (name "MF") "Lite-On Inc.") (field (name "MP") "MOC3063"))
      (libsource (lib "eagle-import") (part "MOC3063S"))
    )
    (comp (ref "U9")
      (value "IR2104")
      (footprint "eagle-import:DIP254P762X533-8")
      (fields (field (name "MF") "Infineon Technologies"))
      (libsource (lib "eagle-import") (part "IR2104"))
    )
    (comp (ref "U10")
      (value "MOC3063S")
      (footprint "eagle-import:DIP762W50P254L730H500Q6")
      (fields (field (name "MF") "Lite-On Inc.") (field (name "MP") "MOC3063"))
      (libsource (lib "eagle-import") (part "MOC3063S"))
    )
    (comp (ref "U11")
      (value "ACS712ELCTR15AT")
      (footprint "eagle-import:SOIC127P600X175-8N")
      (fields (field (name "MF") "Allegro") (field (name "MP") "ACS712ELCTR-30A-T"))
      (libsource (lib "eagle-import") (part "ACS712ELCTR30AT"))
    )
    (comp (ref "U12")
      (value "ACS712ELCTR15AT")
      (footprint "eagle-import:SOIC127P600X175-8N")
      (fields (field (name "MF") "Allegro") (field (name "MP") "ACS712ELCTR-30A-T"))
      (libsource (lib "eagle-import") (part "ACS712ELCTR30AT"))
    )
    (comp (ref "U13")
      (value "VO3120")
      (footprint "eagle-import:DIP762W50P254L977H451Q8")
      (fields (field (name "MF") "Vishay Semiconductor"))
      (libsource (lib "eagle-import") (part "VO3120"))
    )
    (comp (ref "U14")
      (value "ESP32-DEVKITC-32D")
      (footprint "eagle-import:MODULE_ESP32-DEVKITC-32D")
      (fields (field (name "MF") "Espressif Systems"))
      (libsource (lib "eagle-import") (part "ESP32-DEVKITC-32D"))
    )
    (comp (ref "X1")
      (value "nextion_lcd")
      (footprint "eagle-import:22-23-2041")
      (fields (field (name "MF") "MOLEX") (field (name "MPN") "22-23-2041"))
      (libsource (lib "eagle-import") (part "22-23-2041"))
    )
    (comp (ref "X2")
      (value "MKDSN1,5/9-5,08")
      (footprint "eagle-import:MKDSN1,5_9-5,08")
      (libsource (lib "eagle-import") (part "MKDSN1,5/9-5,08"))
    )
    (comp (ref "X3")
      (value "W237-112")
      (footprint "eagle-import:W237-112")
      (fields (field (name "MPN") "237-112"))
      (libsource (lib "eagle-import") (part "W237-112"))
    )
    (comp (ref "X4")
      (value "W237-112")
      (footprint "eagle-import:W237-112")
      (fields (field (name "MPN") "237-112"))
      (libsource (lib "eagle-import") (part "W237-112"))
    )
    (comp (ref "X5")
      (value "MKDSN1,5/9-5,08")
      (footprint "eagle-import:MKDSN1,5_9-5,08")
      (fields (field (name "SPICEPREFIX") "X"))
      (libsource (lib "eagle-import") (part "MKDSN1,5/9-5,08"))
    )
    (comp (ref "X6")
      (value "MKDSN1,5/4-5,08")
      (footprint "eagle-import:MKDSN1,5_4-5,08")
      (libsource (lib "eagle-import") (part "MKDSN1,5/4-5,08"))
    )
    (comp (ref "X8")
      (value "W237-112")
      (footprint "eagle-import:W237-112")
      (fields (field (name "MPN") "237-112"))
      (libsource (lib "eagle-import") (part "W237-112"))
    )
    (comp (ref "X12")
      (value "W237-112")
      (footprint "eagle-import:W237-112")
      (fields (field (name "MPN") "237-112"))
      (libsource (lib "eagle-import") (part "W237-112"))
    )
  )
  (nets
    (net (code "1") (name "+3V3") (class "Default")
      (node (ref "C7") (pin "1") (pinfunction "1_1") (pintype "passive"))
      (node (ref "R3") (pin "2") (pinfunction "2_2") (pintype "passive"))
      (node (ref "R4") (pin "2") (pinfunction "2_2") (pintype "passive"))
      (node (ref "U1") (pin "2") (pinfunction "VOUT_2") (pintype "output"))
    )
    (net (code "2") (name "+5V") (class "Default")
      (node (ref "C17") (pin "1") (pinfunction "1_1") (pintype "passive"))
      (node (ref "C21") (pin "1") (pinfunction "1_1") (pintype "passive"))
      (node (ref "C29") (pin "1") (pinfunction "1_1") (pintype "passive"))
      (node (ref "C31") (pin "1") (pinfunction "1_1") (pintype "passive"))
      (node (ref "C35") (pin "1") (pinfunction "1_1") (pintype "passive"))
      (node (ref "C4") (pin "+") (pinfunction "+_+") (pintype "passive"))
      (node (ref "C6") (pin "1") (pinfunction "1_1") (pintype "passive"))
      (node (ref "IC2") (pin "8") (pinfunction "VDD2_8") (pintype "power_in"))
      (node (ref "J1") (pin "3") (pinfunction "3_3") (pintype "passive"))
      (node (ref "J2") (pin "3") (pinfunction "3_3") (pintype "passive"))
      (node (ref "OK2") (pin "4") (pinfunction "COL_4") (pintype "passive"))
      (node (ref "R49") (pin "1") (pinfunction "1_1") (pintype "passive"))
      (node (ref "U$2") (pin "OUT+") (pinfunction "OUT+_OUT+") (pintype "bidirectional"))
      (node (ref "U$3") (pin "P$18") (pinfunction "5V_P$18") (pintype "bidirectional"))
      (node (ref "U$4") (pin "4") (pinfunction "VCC_4") (pintype "power_in"))
      (node (ref "U1") (pin "3") (pinfunction "VIN_3") (pintype "input"))
      (node (ref "U10") (pin "1") (pinfunction "ANODE_1") (pintype "passive"))
      (node (ref "U11") (pin "8") (pinfunction "VCC_8") (pintype "power_in"))
      (node (ref "U12") (pin "8") (pinfunction "VCC_8") (pintype "power_in"))
      (node (ref "U14") (pin "19") (pinfunction "EXT_5V_19") (pintype "power_in"))
      (node (ref "U4") (pin "1") (pinfunction "ANODE_1") (pintype "passive"))
      (node (ref "U5") (pin "1") (pinfunction "ANODE_1") (pintype "passive"))
      (node (ref "U8") (pin "1") (pinfunction "ANODE_1") (pintype "passive"))
      (node (ref "U9") (pin "3") (pinfunction "~{SD}_3") (pintype "input"))
      (node (ref "X1") (pin "4") (pinfunction "S_4") (pintype "passive"))
    )
    (net (code "3") (name "+13V") (class "Default")
      (node (ref "C2") (pin "+") (pinfunction "+_+") (pintype "passive"))
      (node (ref "C3") (pin "+") (pinfunction "+_+") (pintype "passive"))
      (node (ref "C8") (pin "1") (pinfunction "1_1") (pintype "passive"))
      (node (ref "L6") (pin "1") (pinfunction "1_1") (pintype "passive"))
      (node (ref "OK1") (pin "4") (pinfunction "COL_4") (pintype "passive"))
      (node (ref "U$1") (pin "OUT+") (pinfunction "OUT+_OUT+") (pintype "bidirectional"))
      (node (ref "U$2") (pin "IN+") (pinfunction "IN+_IN+") (pintype "bidirectional"))
      (node (ref "U7") (pin "8") (pinfunction "VCC_8") (pintype "power_in"))
      (node (ref "U9") (pin "1") (pinfunction "VCC_1") (pintype "power_in"))
      (node (ref "U9") (pin "8") (pinfunction "VB_8") (pintype "power_in"))
    )
    (net (code "4") (name "+17V_ISOLATED") (class "Default")
      (node (ref "C10") (pin "1") (pinfunction "1_1") (pintype "passive"))
      (node (ref "D2") (pin "C") (pinfunction "C_C") (pintype "passive"))
      (node (ref "F5") (pin "2") (pinfunction "2_2") (pintype "passive"))
      (node (ref "F6") (pin "2") (pinfunction "2_2") (pintype "passive"))
    )
    (net (code "5") (name "+48V") (class "Default")
      (node (ref "C18") (pin "+") (pinfunction "+_+") (pintype "passive"))
      (node (ref "C28") (pin "+") (pinfunction "+_+") (pintype "passive"))
      (node (ref "L7") (pin "2") (pinfunction "2_2") (pintype "passive"))
      (node (ref "L8") (pin "2") (pinfunction "2_2") (pintype "passive"))
      (node (ref "L9") (pin "2") (pinfunction "2_2") (pintype "passive"))
      (node (ref "Q5") (pin "S") (pinfunction "S_S") (pintype "passive"))
      (node (ref "R24") (pin "1") (pinfunction "1_1") (pintype "passive"))
      (node (ref "R41") (pin "2") (pinfunction "2_2") (pintype "passive"))
    )
    (net (code "6") (name "/3V3") (class "Default")
      (node (ref "U14") (pin "1") (pinfunction "3V3_1") (pintype "power_in"))
    )
    (net (code "7") (name "/5V") (class "Default")
      (node (ref "C26") (pin "1") (pinfunction "1_1") (pintype "passive"))
      (node (ref "IC1") (pin "1") (pinfunction "VCC_1") (pintype "power_in"))
    )
    (net (code "8") (name "/50K_PWM") (class "Default")
      (node (ref "U$3") (pin "P$5") (pinfunction "PA8_P$5") (pintype "bidirectional"))
      (node (ref "U9") (pin "2") (pinfunction "IN_2") (pintype "input"))
    )
    (net (code "9") (name "/AC_OUT_READ") (class "Default")
      (node (ref "R46") (pin "2") (pinfunction "2_2") (pintype "passive"))
      (node (ref "R47") (pin "2") (pinfunction "2_2") (pintype "passive"))
      (node (ref "U$3") (pin "P$32") (pinfunction "PA4_P$32") (pintype "bidirectional"))
      (node (ref "U14") (pin "7") (pinfunction "IO32_7") (pintype "bidirectional"))
    )
    (net (code "10") (name "/BAT_LEVEL_READ") (class "Default")
      (node (ref "R1") (pin "1") (pinfunction "1_1") (pintype "passive"))
      (node (ref "R2") (pin "2") (pinfunction "2_2") (pintype "passive"))
      (node (ref "U$3") (pin "P$36") (pinfunction "PA0_P$36") (pintype "bidirectional"))
      (node (ref "U14") (pin "5") (pinfunction "IO34_5") (pintype "bidirectional"))
    )
    (net (code "11") (name "/BAT_REGULATE_LEVEL_READ") (class "Default")
      (node (ref "R41") (pin "1") (pinfunction "1_1") (pintype "passive"))
      (node (ref "R42") (pin "2") (pinfunction "2_2") (pintype "passive"))
      (node (ref "U$3") (pin "P$33") (pinfunction "PA3_P$33") (pintype "bidirectional"))
      (node (ref "U14") (pin "6") (pinfunction "IO35_6") (pintype "bidirectional"))
    )
    (net (code "12") (name "/BOOST_PWM") (class "Default")
      (node (ref "Q19") (pin "G") (pinfunction "G_G") (pintype "passive"))
      (node (ref "U$3") (pin "P$30") (pinfunction "PA6_P$30") (pintype "bidirectional"))
    )
    (net (code "13") (name "/CT_1") (class "Default")
      (node (ref "D9") (pin "A") (pinfunction "A_A") (pintype "passive"))
      (node (ref "R57") (pin "1") (pinfunction "1_1") (pintype "passive"))
      (node (ref "T5") (pin "T2") (pinfunction "A2_T2") (pintype "passive"))
      (node (ref "X2") (pin "1") (pinfunction "KL_1") (pintype "passive"))
      (node (ref "X2") (pin "2") (pinfunction "KL_2") (pintype "passive"))
    )
    (net (code "14") (name "/CT_2") (class "Default")
      (node (ref "D8") (pin "C") (pinfunction "C_C") (pintype "passive"))
      (node (ref "Q16") (pin "S") (pinfunction "S_S") (pintype "passive"))
      (node (ref "R50") (pin "2") (pinfunction "2_2") (pintype "passive"))
      (node (ref "R53") (pin "2") (pinfunction "2_2") (pintype "passive"))
      (node (ref "X2") (pin "4") (pinfunction "KL_4") (pintype "passive"))
      (node (ref "X2") (pin "5") (pinfunction "KL_5") (pintype "passive"))
      (node (ref "X2") (pin "6") (pinfunction "KL_6") (pintype "passive"))
    )
    (net (code "15") (name "/CT_3") (class "Default")
      (node (ref "D7") (pin "A") (pinfunction "A_A") (pintype "passive"))
      (node (ref "R60") (pin "1") (pinfunction "1_1") (pintype "passive"))
      (node (ref "T9") (pin "T2") (pinfunction "A2_T2") (pintype "passive"))
      (node (ref "X2") (pin "8") (pinfunction "KL_8") (pintype "passive"))
      (node (ref "X2") (pin "9") (pinfunction "KL_9") (pintype "passive"))
    )
    (net (code "16") (name "/CT_READ") (class "Default")
      (node (ref "C33") (pin "1") (pinfunction "1_1") (pintype "passive"))
      (node (ref "R50") (pin "1") (pinfunction "1_1") (pintype "passive"))
      (node (ref "R51") (pin "2") (pinfunction "2_2") (pintype "passive"))
      (node (ref "U$3") (pin "P$13") (pinfunction "PB5_P$13") (pintype "bidirectional"))
      (node (ref "U14") (pin "8") (pinfunction "IO33_8") (pintype "bidirectional"))
    )
    (net (code "17") (name "/D10") (class "Default")
      (node (ref "D10") (pin "A") (pinfunction "A_A") (pintype "passive"))
      (node (ref "Q10") (pin "D") (pinfunction "D_D") (pintype "passive"))
      (node (ref "Q11") (pin "D") (pinfunction "D_D") (pintype "passive"))
    )
    (net (code "18") (name "/GND_ISOLATED") (class "Default")
      (node (ref "C10") (pin "2") (pinfunction "2_2") (pintype "passive"))
      (node (ref "C11") (pin "2") (pinfunction "2_2") (pintype "passive"))
      (node (ref "C13") (pin "2") (pinfunction "2_2") (pintype "passive"))
      (node (ref "C14") (pin "2") (pinfunction "2_2") (pintype "passive"))
      (node (ref "C15") (pin "2") (pinfunction "2_2") (pintype "passive"))
      (node (ref "C16") (pin "2") (pinfunction "2_2") (pintype "passive"))
      (node (ref "C9") (pin "2") (pinfunction "2_2") (pintype "passive"))
      (node (ref "D3") (pin "A") (pinfunction "A_A") (pintype "passive"))
      (node (ref "D5") (pin "A") (pinfunction "A_A") (pintype "passive"))
      (node (ref "L6") (pin "4") (pinfunction "2_4") (pintype "passive"))
      (node (ref "Q7") (pin "S") (pinfunction "S_S") (pintype "passive"))
      (node (ref "Q9") (pin "S") (pinfunction "S_S") (pintype "passive"))
      (node (ref "U2") (pin "5") (pinfunction "VEE_5") (pintype "power_in"))
      (node (ref "U3") (pin "5") (pinfunction "VEE_5") (pintype "power_in"))
    )
    (net (code "19") (name "/INPUT") (class "Default")
      (node (ref "F1") (pin "1") (pinfunction "1_1") (pintype "passive"))
      (node (ref "X3") (pin "1") (pinfunction "KL_1") (pintype "passive"))
    )
    (net (code "20") (name "/INPUT_SAFETY") (class "Default")
      (node (ref "C1") (pin "+") (pinfunction "+_+") (pintype "passive"))
      (node (ref "IC1") (pin "IP-") (pinfunction "IP-_IP-") (pintype "passive"))
      (node (ref "IC1") (pin "IP-@10") (pinfunction "IP-_IP-@10") (pintype "passive"))
      (node (ref "IC1") (pin "IP-@11") (pinfunction "IP-_IP-@11") (pintype "passive"))
      (node (ref "IC1") (pin "IP-@12") (pinfunction "IP-_IP-@12") (pintype "passive"))
      (node (ref "IC1") (pin "IP-@13") (pinfunction "IP-_IP-@13") (pintype "passive"))
      (node (ref "IC1") (pin "IP-@14") (pinfunction "IP-_IP-@14") (pintype "passive"))
      (node (ref "IC1") (pin "IP-@15") (pinfunction "IP-_IP-@15") (pintype "passive"))
      (node (ref "IC1") (pin "IP-@16") (pinfunction "IP-_IP-@16") (pintype "passive"))
      (node (ref "IC1") (pin "IP-@17") (pinfunction "IP-_IP-@17") (pintype "passive"))
      (node (ref "IC1") (pin "IP-@2") (pinfunction "IP-_IP-@2") (pintype "passive"))
      (node (ref "IC1") (pin "IP-@3") (pinfunction "IP-_IP-@3") (pintype "passive"))
      (node (ref "IC1") (pin "IP-@4") (pinfunction "IP-_IP-@4") (pintype "passive"))
      (node (ref "IC1") (pin "IP-@5") (pinfunction "IP-_IP-@5") (pintype "passive"))
      (node (ref "IC1") (pin "IP-@6") (pinfunction "IP-_IP-@6") (pintype "passive"))
      (node (ref "IC1") (pin "IP-@7") (pinfunction "IP-_IP-@7") (pintype "passive"))
      (node (ref "IC1") (pin "IP-@8") (pinfunction "IP-_IP-@8") (pintype "passive"))
      (node (ref "IC1") (pin "IP-@9") (pinfunction "IP-_IP-@9") (pintype "passive"))
      (node (ref "Q10") (pin "S") (pinfunction "S_S") (pintype "passive"))
      (node (ref "Q11") (pin "S") (pinfunction "S_S") (pintype "passive"))
      (node (ref "R1") (pin "2") (pinfunction "2_2") (pintype "passive"))
      (node (ref "R30") (pin "2") (pinfunction "2_2") (pintype "passive"))
      (node (ref "R55") (pin "2") (pinfunction "2_2") (pintype "passive"))
      (node (ref "U$1") (pin "IN+") (pinfunction "IN+_IN+") (pintype "bidirectional"))
    )
    (net (code "21") (name "/ISOLATED_PWM") (class "Default")
      (node (ref "R21") (pin "1") (pinfunction "1_1") (pintype "passive"))
      (node (ref "U$3") (pin "P$6") (pinfunction "PA9_P$6") (pintype "bidirectional"))
    )
    (net (code "22") (name "/MOS_48") (class "Default")
      (node (ref "D8") (pin "A") (pinfunction "A_A") (pintype "passive"))
      (node (ref "Q5") (pin "D") (pinfunction "D_D") (pintype "passive"))
    )
    (net (code "23") (name "/PLN_1") (class "Default")
      (node (ref "D12") (pin "C") (pinfunction "C_C") (pintype "passive"))
      (node (ref "R17") (pin "1") (pinfunction "1_1") (pintype "passive"))
      (node (ref "T1") (pin "T2") (pinfunction "A2_T2") (pintype "passive"))
      (node (ref "X5") (pin "1") (pinfunction "KL_1") (pintype "passive"))
      (node (ref "X5") (pin "2") (pinfunction "KL_2") (pintype "passive"))
    )
    (net (code "24") (name "/PLN_2") (class "Default")
      (node (ref "D13") (pin "A") (pinfunction "A_A") (pintype "passive"))
      (node (ref "R35") (pin "2") (pinfunction "2_2") (pintype "passive"))
      (node (ref "T3") (pin "T2") (pinfunction "A2_T2") (pintype "passive"))
      (node (ref "X5") (pin "8") (pinfunction "KL_8") (pintype "passive"))
      (node (ref "X5") (pin "9") (pinfunction "KL_9") (pintype "passive"))
    )
    (net (code "25") (name "/REVERSE_MODE_CONTROL") (class "Default")
      (node (ref "R26") (pin "1") (pinfunction "1_1") (pintype "passive"))
      (node (ref "T13") (pin "B") (pinfunction "B_B") (pintype "passive"))
      (node (ref "T15") (pin "B") (pinfunction "B_B") (pintype "passive"))
      (node (ref "T2") (pin "B") (pinfunction "B_B") (pintype "passive"))
      (node (ref "U$3") (pin "P$11") (pinfunction "PB3_P$11") (pintype "bidirectional"))
    )
    (net (code "26") (name "/REVERSE_PLN") (class "Default")
      (node (ref "R27") (pin "1") (pinfunction "1_1") (pintype "passive"))
      (node (ref "R28") (pin "1") (pinfunction "1_1") (pintype "passive"))
      (node (ref "U13") (pin "6") (pinfunction "VO1_6") (pintype "passive"))
      (node (ref "U13") (pin "7") (pinfunction "VO2_7") (pintype "passive"))
    )
    (net (code "27") (name "/SPWM_A") (class "Default")
      (node (ref "U$3") (pin "P$35") (pinfunction "PA1_P$35") (pintype "bidirectional"))
      (node (ref "U2") (pin "3") (pinfunction "C_3") (pintype "passive"))
    )
    (net (code "28") (name "/SPWM_A_OUT") (class "Default")
      (node (ref "Q14") (pin "G") (pinfunction "G_G") (pintype "passive"))
      (node (ref "Q9") (pin "G") (pinfunction "G_G") (pintype "passive"))
      (node (ref "R19") (pin "1") (pinfunction "1_1") (pintype "passive"))
    )
    (net (code "29") (name "/SPWM_B") (class "Default")
      (node (ref "U$3") (pin "P$34") (pinfunction "PA2_P$34") (pintype "bidirectional"))
      (node (ref "U3") (pin "3") (pinfunction "C_3") (pintype "passive"))
    )
    (net (code "30") (name "/SPWM_B_OUT") (class "Default")
      (node (ref "Q7") (pin "G") (pinfunction "G_G") (pintype "passive"))
      (node (ref "Q8") (pin "G") (pinfunction "G_G") (pintype "passive"))
      (node (ref "R20") (pin "1") (pinfunction "1_1") (pintype "passive"))
    )
    (net (code "31") (name "/TEMP_1_READ") (class "Default")
      (node (ref "J1") (pin "2") (pinfunction "2_2") (pintype "passive"))
      (node (ref "U$3") (pin "P$28") (pinfunction "PB0_P$28") (pintype "bidirectional"))
      (node (ref "U14") (pin "9") (pinfunction "IO25_9") (pintype "bidirectional"))
    )
    (net (code "32") (name "/TEMP_2_READ") (class "Default")
      (node (ref "J2") (pin "2") (pinfunction "2_2") (pintype "passive"))
      (node (ref "U$3") (pin "P$27") (pinfunction "PB1_P$27") (pintype "bidirectional"))
      (node (ref "U14") (pin "10") (pinfunction "IO26_10") (pintype "bidirectional"))
    )
    (net (code "33") (name "/VIN+") (class "Default")
      (node (ref "IC2") (pin "2") (pinfunction "VIN+_2") (pintype "power_in"))
    )
    (net (code "34") (name "/VIN-") (class "Default")
      (node (ref "IC2") (pin "3") (pinfunction "VIN-_3") (pintype "power_in"))
    )
    (net (code "35") (name "/VOUT+") (class "Default")
      (node (ref "IC2") (pin "7") (pinfunction "VOUT+_7") (pintype "power_in"))
    )
    (net (code "36") (name "0V") (class "Default")
      (node (ref "B2") (pin "-") (pinfunction "-_-") (pintype "passive"))
      (node (ref "C12") (pin "2") (pinfunction "2_2") (pintype "passive"))
      (node (ref "C19") (pin "2") (pinfunction "2_2") (pintype "passive"))
      (node (ref "C22") (pin "-") (pinfunction "-_-") (pintype "passive"))
      (node (ref "C23") (pin "-") (pinfunction "-_-") (pintype "passive"))
      (node (ref "C32") (pin "-") (pinfunction "-_-") (pintype "passive"))
      (node (ref "PS1") (pin "3") (pinfunction "-VO_3") (pintype "output"))
      (node (ref "Q15") (pin "S") (pinfunction "S_S") (pintype "passive"))
      (node (ref "Q4") (pin "S") (pinfunction "S_S") (pintype "passive"))
      (node (ref "R29") (pin "1") (pinfunction "1_1") (pintype "passive"))
      (node (ref "R32") (pin "1") (pinfunction "1_1") (pintype "passive"))
      (node (ref "U13") (pin "5") (pinfunction "VEE_5") (pintype "power_in"))
      (node (ref "U6") (pin "4") (pinfunction "COM_4") (pintype "power_in"))
    )
    (net (code "37") (name "BATTERY_INPUT_PWM") (class "Default")
      (node (ref "R54") (pin "1") (pinfunction "1_1") (pintype "passive"))
      (node (ref "U$3") (pin "P$14") (pinfunction "PB6_P$14") (pintype "bidirectional"))
    )
    (net (code "38") (name "BAT_CURRENT_READ") (class "Default")
      (node (ref "C26") (pin "2") (pinfunction "2_2") (pintype "passive"))
      (node (ref "C5") (pin "1") (pinfunction "1_1") (pintype "passive"))
      (node (ref "R22") (pin "2") (pinfunction "2_2") (pintype "passive"))
      (node (ref "U14") (pin "11") (pinfunction "IO27_11") (pintype "bidirectional"))
    )
    (net (code "39") (name "CHARGING_CURRENT_READ") (class "Default")
      (node (ref "U12") (pin "7") (pinfunction "VIOUT_7") (pintype "output"))
      (node (ref "U14") (pin "32") (pinfunction "IO4_32") (pintype "bidirectional"))
    )
    (net (code "40") (name "FORWARD_MODE_CONTROL") (class "Default")
      (node (ref "R33") (pin "1") (pinfunction "1_1") (pintype "passive"))
      (node (ref "T4") (pin "B") (pinfunction "B_B") (pintype "passive"))
      (node (ref "T7") (pin "B") (pinfunction "B_B") (pintype "passive"))
      (node (ref "T8") (pin "B") (pinfunction "B_B") (pintype "passive"))
      (node (ref "U$3") (pin "P$12") (pinfunction "PB4_P$12") (pintype "bidirectional"))
    )
    (net (code "41") (name "FREQUENCY_OUT_READ") (class "Default")
      (node (ref "IC2") (pin "6") (pinfunction "VOUT-_6") (pintype "power_in"))
      (node (ref "U14") (pin "15") (pinfunction "IO13_15") (pintype "bidirectional"))
    )
    (net (code "42") (name "GND") (class "Default")
      (node (ref "C1") (pin "-") (pinfunction "-_-") (pintype "passive"))
      (node (ref "C17") (pin "2") (pinfunction "2_2") (pintype "passive"))
      (node (ref "C18") (pin "-") (pinfunction "-_-") (pintype "passive"))
      (node (ref "C2") (pin "-") (pinfunction "-_-") (pintype "passive"))
      (node (ref "C21") (pin "2") (pinfunction "2_2") (pintype "passive"))
      (node (ref "C28") (pin "-") (pinfunction "-_-") (pintype "passive"))
      (node (ref "C29") (pin "2") (pinfunction "2_2") (pintype "passive"))
      (node (ref "C3") (pin "-") (pinfunction "-_-") (pintype "passive"))
      (node (ref "C30") (pin "2") (pinfunction "2_2") (pintype "passive"))
      (node (ref "C31") (pin "2") (pinfunction "2_2") (pintype "passive"))
      (node (ref "C33") (pin "2") (pinfunction "2_2") (pintype "passive"))
      (node (ref "C34") (pin "2") (pinfunction "2_2") (pintype "passive"))
      (node (ref "C35") (pin "2") (pinfunction "2_2") (pintype "passive"))
      (node (ref "C4") (pin "-") (pinfunction "-_-") (pintype "passive"))
      (node (ref "C5") (pin "2") (pinfunction "2_2") (pintype "passive"))
      (node (ref "C6") (pin "2") (pinfunction "2_2") (pintype "passive"))
      (node (ref "C7") (pin "2") (pinfunction "2_2") (pintype "passive"))
      (node (ref "C8") (pin "2") (pinfunction "2_2") (pintype "passive"))
      (node (ref "IC1") (pin "2") (pinfunction "GND_2") (pintype "power_in"))
      (node (ref "IC2") (pin "5") (pinfunction "GND2_5") (pintype "power_in"))
      (node (ref "J1") (pin "1") (pinfunction "1_1") (pintype "passive"))
      (node (ref "J2") (pin "1") (pinfunction "1_1") (pintype "passive"))
      (node (ref "LED3") (pin "C") (pinfunction "C_C") (pintype "passive"))
      (node (ref "OK2") (pin "2") (pinfunction "C_2") (pintype "passive"))
      (node (ref "Q1") (pin "S") (pinfunction "S_S") (pintype "passive"))
      (node (ref "Q2") (pin "S") (pinfunction "S_S") (pintype "passive"))
      (node (ref "Q20") (pin "S") (pinfunction "S_S") (pintype "passive"))
      (node (ref "Q21") (pin "S") (pinfunction "S_S") (pintype "passive"))
      (node (ref "Q22") (pin "S") (pinfunction "S_S") (pintype "passive"))
      (node (ref "Q23") (pin "S") (pinfunction "S_S") (pintype "passive"))
      (node (ref "Q3") (pin "S") (pinfunction "S_S") (pintype "passive"))
      (node (ref "R13") (pin "2") (pinfunction "2_2") (pintype "passive"))
      (node (ref "R14") (pin "2") (pinfunction "2_2") (pintype "passive"))
      (node (ref "R15") (pin "2") (pinfunction "2_2") (pintype "passive"))
      (node (ref "R16") (pin "2") (pinfunction "2_2") (pintype "passive"))
      (node (ref "R2") (pin "1") (pinfunction "1_1") (pintype "passive"))
      (node (ref "R42") (pin "1") (pinfunction "1_1") (pintype "passive"))
      (node (ref "R47") (pin "1") (pinfunction "1_1") (pintype "passive"))
      (node (ref "R5") (pin "2") (pinfunction "2_2") (pintype "passive"))
      (node (ref "R51") (pin "1") (pinfunction "1_1") (pintype "passive"))
      (node (ref "R7") (pin "2") (pinfunction "2_2") (pintype "passive"))
      (node (ref "T11") (pin "E") (pinfunction "E_E") (pintype "passive"))
      (node (ref "T13") (pin "E") (pinfunction "E_E") (pintype "passive"))
      (node (ref "T15") (pin "E") (pinfunction "E_E") (pintype "passive"))
      (node (ref "T2") (pin "E") (pinfunction "E_E") (pintype "passive"))
      (node (ref "T4") (pin "E") (pinfunction "E_E") (pintype "passive"))
      (node (ref "T6") (pin "E") (pinfunction "E_E") (pintype "passive"))
      (node (ref "T7") (pin "E") (pinfunction "E_E") (pintype "passive"))
      (node (ref "T8") (pin "E") (pinfunction "E_E") (pintype "passive"))
      (node (ref "U$1") (pin "IN-") (pinfunction "IN-_IN-") (pintype "bidirectional"))
      (node (ref "U$1") (pin "OUT-") (pinfunction "OUT-_OUT-") (pintype "bidirectional"))
      (node (ref "U$2") (pin "IN-") (pinfunction "IN-_IN-") (pintype "bidirectional"))
      (node (ref "U$2") (pin "OUT-") (pinfunction "OUT-_OUT-") (pintype "bidirectional"))
      (node (ref "U$3") (pin "P$19") (pinfunction "GND2_P$19") (pintype "bidirectional"))
      (node (ref "U$3") (pin "P$21") (pinfunction "GND1_P$21") (pintype "power_in"))
      (node (ref "U$3") (pin "P$22") (pinfunction "GND_P$22") (pintype "bidirectional"))
      (node (ref "U$4") (pin "1") (pinfunction "GND.2_1") (pintype "power_in"))
      (node (ref "U$4") (pin "2") (pinfunction "GND.1_2") (pintype "power_in"))
      (node (ref "U1") (pin "1") (pinfunction "ADJ/GND_1") (pintype "power_in"))
      (node (ref "U11") (pin "5") (pinfunction "GND_5") (pintype "power_in"))
      (node (ref "U12") (pin "5") (pinfunction "GND_5") (pintype "power_in"))
      (node (ref "U13") (pin "3") (pinfunction "C_3") (pintype "passive"))
      (node (ref "U14") (pin "14") (pinfunction "GND1_14") (pintype "power_in"))
      (node (ref "U14") (pin "20") (pinfunction "GND3_20") (pintype "power_in"))
      (node (ref "U14") (pin "26") (pinfunction "GND2_26") (pintype "power_in"))
      (node (ref "U7") (pin "3") (pinfunction "C_3") (pintype "passive"))
      (node (ref "U7") (pin "5") (pinfunction "VEE_5") (pintype "power_in"))
      (node (ref "U9") (pin "4") (pinfunction "COM_4") (pintype "input"))
      (node (ref "U9") (pin "6") (pinfunction "VS_6") (pintype "power_in"))
      (node (ref "X1") (pin "1") (pinfunction "S_1") (pintype "passive"))
      (node (ref "X4") (pin "1") (pinfunction "KL_1") (pintype "passive"))
    )
    (net (code "43") (name "INVERTER_CURRENT_READ") (class "Default")
      (node (ref "U11") (pin "7") (pinfunction "VIOUT_7") (pintype "output"))
      (node (ref "U14") (pin "12") (pinfunction "IO14_12") (pintype "bidirectional"))
    )
    (net (code "44") (name "Net-(B2-Pad+)") (class "Default")
      (node (ref "B2") (pin "+") (pinfunction "+_+") (pintype "passive"))
      (node (ref "C23") (pin "+") (pinfunction "+_+") (pintype "passive"))
      (node (ref "Q13") (pin "D") (pinfunction "D_D") (pintype "passive"))
      (node (ref "R45") (pin "1") (pinfunction "1_1") (pintype "passive"))
    )
    (net (code "45") (name "Net-(C9-Pad1)") (class "Default")
      (node (ref "C9") (pin "1") (pinfunction "1_1") (pintype "passive"))
      (node (ref "D2") (pin "A") (pinfunction "A_A") (pintype "passive"))
      (node (ref "L6") (pin "3") (pinfunction "3_3") (pintype "passive"))
    )
    (net (code "46") (name "Net-(C11-Pad1)") (class "Default")
      (node (ref "C11") (pin "1") (pinfunction "1_1") (pintype "passive"))
      (node (ref "C13") (pin "1") (pinfunction "1_1") (pintype "passive"))
      (node (ref "C15") (pin "1") (pinfunction "1_1") (pintype "passive"))
      (node (ref "L1") (pin "2") (pinfunction "2_2") (pintype "passive"))
      (node (ref "Q14") (pin "D") (pinfunction "D_D") (pintype "passive"))
      (node (ref "Q8") (pin "D") (pinfunction "D_D") (pintype "passive"))
    )
    (net (code "47") (name "Net-(C24-Pad1)") (class "Default")
      (node (ref "C24") (pin "1") (pinfunction "1_1") (pintype "passive"))
      (node (ref "Q13") (pin "S") (pinfunction "S_S") (pintype "passive"))
      (node (ref "Q15") (pin "D") (pinfunction "D_D") (pintype "passive"))
    )
    (net (code "48") (name "Net-(C24-Pad2)") (class "Default")
      (node (ref "C24") (pin "2") (pinfunction "2_2") (pintype "passive"))
      (node (ref "Q6") (pin "D") (pinfunction "D_D") (pintype "passive"))
    )
    (net (code "49") (name "Net-(C25-Pad+)") (class "Default")
      (node (ref "C25") (pin "+") (pinfunction "+_+") (pintype "passive"))
      (node (ref "L3") (pin "2") (pinfunction "2_2") (pintype "passive"))
      (node (ref "L5") (pin "1") (pinfunction "1_1") (pintype "passive"))
    )
    (net (code "50") (name "Net-(C27-Pad1)") (class "Default")
      (node (ref "C27") (pin "1") (pinfunction "1_1") (pintype "passive"))
      (node (ref "D15") (pin "C") (pinfunction "C_C") (pintype "passive"))
      (node (ref "U12") (pin "1") (pinfunction "IP+_1") (pintype "input"))
      (node (ref "U12") (pin "2") (pinfunction "IP+_2") (pintype "input"))
    )
    (net (code "51") (name "Net-(D4-PadC)") (class "Default")
      (node (ref "D4") (pin "C") (pinfunction "C_C") (pintype "passive"))
      (node (ref "D6") (pin "C") (pinfunction "C_C") (pintype "passive"))
      (node (ref "L1") (pin "1") (pinfunction "1_1") (pintype "passive"))
    )
    (net (code "52") (name "Net-(D7-PadC)") (class "Default")
      (node (ref "D7") (pin "C") (pinfunction "C_C") (pintype "passive"))
      (node (ref "Q21") (pin "D") (pinfunction "D_D") (pintype "passive"))
      (node (ref "Q22") (pin "D") (pinfunction "D_D") (pintype "passive"))
      (node (ref "Q23") (pin "D") (pinfunction "D_D") (pintype "passive"))
    )
    (net (code "53") (name "Net-(D9-PadC)") (class "Default")
      (node (ref "D9") (pin "C") (pinfunction "C_C") (pintype "passive"))
      (node (ref "Q1") (pin "D") (pinfunction "D_D") (pintype "passive"))
      (node (ref "Q2") (pin "D") (pinfunction "D_D") (pintype "passive"))
      (node (ref "Q3") (pin "D") (pinfunction "D_D") (pintype "passive"))
    )
    (net (code "54") (name "Net-(D10-PadC)") (class "Default")
      (node (ref "D10") (pin "C") (pinfunction "C_C") (pintype "passive"))
      (node (ref "L7") (pin "1") (pinfunction "1_1") (pintype "passive"))
      (node (ref "L8") (pin "1") (pinfunction "1_1") (pintype "passive"))
      (node (ref "L9") (pin "1") (pinfunction "1_1") (pintype "passive"))
    )
    (net (code "55") (name "Net-(D12-PadA)") (class "Default")
      (node (ref "D12") (pin "A") (pinfunction "A_A") (pintype "passive"))
      (node (ref "Q6") (pin "S") (pinfunction "S_S") (pintype "passive"))
    )
    (net (code "56") (name "Net-(D13-PadC)") (class "Default")
      (node (ref "D13") (pin "C") (pinfunction "C_C") (pintype "passive"))
      (node (ref "Q4") (pin "D") (pinfunction "D_D") (pintype "passive"))
    )
    (net (code "57") (name "Net-(D14-PadC)") (class "Default")
      (node (ref "D14") (pin "C") (pinfunction "C_C") (pintype "passive"))
      (node (ref "D16") (pin "C") (pinfunction "C_C") (pintype "passive"))
      (node (ref "L3") (pin "1") (pinfunction "1_1") (pintype "passive"))
    )
    (net (code "58") (name "Net-(D15-PadA)") (class "Default")
      (node (ref "D15") (pin "A") (pinfunction "A_A") (pintype "passive"))
      (node (ref "L5") (pin "2") (pinfunction "2_2") (pintype "passive"))
      (node (ref "Q19") (pin "D") (pinfunction "D_D") (pintype "passive"))
    )
    (net (code "59") (name "Net-(DC_PLN+-KL)") (class "Default")
      (node (ref "DC_PLN+") (pin "1") (pinfunction "KL_1") (pintype "passive"))
      (node (ref "U12") (pin "3") (pinfunction "IP-_3") (pintype "input"))
      (node (ref "U12") (pin "4") (pinfunction "IP-_4") (pintype "input"))
    )
    (net (code "60") (name "Net-(DC_PLN--KL)") (class "Default")
      (node (ref "C25") (pin "-") (pinfunction "-_-") (pintype "passive"))
      (node (ref "C27") (pin "2") (pinfunction "2_2") (pintype "passive"))
      (node (ref "DC_PLN-") (pin "1") (pinfunction "KL_1") (pintype "passive"))
      (node (ref "Q12") (pin "S") (pinfunction "S_S") (pintype "passive"))
      (node (ref "Q19") (pin "S") (pinfunction "S_S") (pintype "passive"))
      (node (ref "R52") (pin "1") (pinfunction "1_1") (pintype "passive"))
    )
    (net (code "61") (name "Net-(F1-Pad2)") (class "Default")
      (node (ref "F1") (pin "2") (pinfunction "2_2") (pintype "passive"))
      (node (ref "IC1") (pin "IP+") (pinfunction "IP+_IP+") (pintype "passive"))
      (node (ref "IC1") (pin "IP+@10") (pinfunction "IP+_IP+@10") (pintype "passive"))
      (node (ref "IC1") (pin "IP+@11") (pinfunction "IP+_IP+@11") (pintype "passive"))
      (node (ref "IC1") (pin "IP+@12") (pinfunction "IP+_IP+@12") (pintype "passive"))
      (node (ref "IC1") (pin "IP+@13") (pinfunction "IP+_IP+@13") (pintype "passive"))
      (node (ref "IC1") (pin "IP+@14") (pinfunction "IP+_IP+@14") (pintype "passive"))
      (node (ref "IC1") (pin "IP+@15") (pinfunction "IP+_IP+@15") (pintype "passive"))
      (node (ref "IC1") (pin "IP+@16") (pinfunction "IP+_IP+@16") (pintype "passive"))
      (node (ref "IC1") (pin "IP+@17") (pinfunction "IP+_IP+@17") (pintype "passive"))
      (node (ref "IC1") (pin "IP+@2") (pinfunction "IP+_IP+@2") (pintype "passive"))
      (node (ref "IC1") (pin "IP+@3") (pinfunction "IP+_IP+@3") (pintype "passive"))
      (node (ref "IC1") (pin "IP+@4") (pinfunction "IP+_IP+@4") (pintype "passive"))
      (node (ref "IC1") (pin "IP+@5") (pinfunction "IP+_IP+@5") (pintype "passive"))
      (node (ref "IC1") (pin "IP+@6") (pinfunction "IP+_IP+@6") (pintype "passive"))
      (node (ref "IC1") (pin "IP+@7") (pinfunction "IP+_IP+@7") (pintype "passive"))
      (node (ref "IC1") (pin "IP+@8") (pinfunction "IP+_IP+@8") (pintype "passive"))
      (node (ref "IC1") (pin "IP+@9") (pinfunction "IP+_IP+@9") (pintype "passive"))
    )
    (net (code "62") (name "Net-(F2-Pad1)") (class "Default")
      (node (ref "F2") (pin "1") (pinfunction "1_1") (pintype "passive"))
      (node (ref "R10") (pin "2") (pinfunction "2_2") (pintype "passive"))
      (node (ref "R8") (pin "2") (pinfunction "2_2") (pintype "passive"))
      (node (ref "R9") (pin "2") (pinfunction "2_2") (pintype "passive"))
    )
    (net (code "63") (name "Net-(F3-Pad1)") (class "Default")
      (node (ref "F3") (pin "1") (pinfunction "1_1") (pintype "passive"))
      (node (ref "R11") (pin "2") (pinfunction "2_2") (pintype "passive"))
      (node (ref "R12") (pin "2") (pinfunction "2_2") (pintype "passive"))
      (node (ref "R6") (pin "2") (pinfunction "2_2") (pintype "passive"))
    )
    (net (code "64") (name "Net-(F4-Pad1)") (class "Default")
      (node (ref "F4") (pin "1") (pinfunction "1_1") (pintype "passive"))
      (node (ref "Q14") (pin "S") (pinfunction "S_S") (pintype "passive"))
      (node (ref "Q7") (pin "D") (pinfunction "D_D") (pintype "passive"))
    )
    (net (code "65") (name "Net-(IC1-VOUT)") (class "Default")
      (node (ref "IC1") (pin "3") (pinfunction "VOUT_3") (pintype "output"))
      (node (ref "R22") (pin "1") (pinfunction "1_1") (pintype "passive"))
    )
    (net (code "66") (name "Net-(IC2-GND1)") (class "Default")
      (node (ref "IC2") (pin "4") (pinfunction "GND1_4") (pintype "power_in"))
      (node (ref "R44") (pin "2") (pinfunction "2_2") (pintype "passive"))
    )
    (net (code "67") (name "Net-(IC2-VDD1)") (class "Default")
      (node (ref "IC2") (pin "1") (pinfunction "VDD1_1") (pintype "power_in"))
      (node (ref "R43") (pin "2") (pinfunction "2_2") (pintype "passive"))
    )
    (net (code "68") (name "Net-(L6-4)") (class "Default")
      (node (ref "L6") (pin "2") (pinfunction "4_2") (pintype "passive"))
      (node (ref "Q20") (pin "D") (pinfunction "D_D") (pintype "passive"))
    )
    (net (code "69") (name "Net-(LED3-PadA)") (class "Default")
      (node (ref "LED3") (pin "A") (pinfunction "A_A") (pintype "passive"))
      (node (ref "R33") (pin "2") (pinfunction "2_2") (pintype "passive"))
    )
    (net (code "70") (name "Net-(LED5-PadC)") (class "Default")
      (node (ref "LED5") (pin "C") (pinfunction "C_C") (pintype "passive"))
      (node (ref "R39") (pin "2") (pinfunction "2_2") (pintype "passive"))
    )
    (net (code "71") (name "Net-(LED6-PadC)") (class "Default")
      (node (ref "LED6") (pin "C") (pinfunction "C_C") (pintype "passive"))
      (node (ref "R40") (pin "2") (pinfunction "2_2") (pintype "passive"))
    )
    (net (code "72") (name "Net-(LED9-PadC)") (class "Default")
      (node (ref "LED9") (pin "C") (pinfunction "C_C") (pintype "passive"))
      (node (ref "R59") (pin "2") (pinfunction "2_2") (pintype "passive"))
    )
    (net (code "73") (name "Net-(LED10-PadC)") (class "Default")
      (node (ref "LED10") (pin "C") (pinfunction "C_C") (pintype "passive"))
      (node (ref "R62") (pin "2") (pinfunction "2_2") (pintype "passive"))
    )
    (net (code "74") (name "Net-(OK1-A)") (class "Default")
      (node (ref "OK1") (pin "1") (pinfunction "A_1") (pintype "passive"))
      (node (ref "R49") (pin "2") (pinfunction "2_2") (pintype "passive"))
    )
    (net (code "75") (name "Net-(OK1-C)") (class "Default")
      (node (ref "OK1") (pin "2") (pinfunction "C_2") (pintype "passive"))
      (node (ref "T2") (pin "C") (pinfunction "C_C") (pintype "passive"))
    )
    (net (code "76") (name "Net-(OK1-EMIT)") (class "Default")
      (node (ref "OK1") (pin "3") (pinfunction "EMIT_3") (pintype "passive"))
      (node (ref "R23") (pin "2") (pinfunction "2_2") (pintype "passive"))
      (node (ref "R48") (pin "2") (pinfunction "2_2") (pintype "passive"))
    )
    (net (code "77") (name "Net-(OK2-A)") (class "Default")
      (node (ref "OK2") (pin "1") (pinfunction "A_1") (pintype "passive"))
      (node (ref "R54") (pin "2") (pinfunction "2_2") (pintype "passive"))
    )
    (net (code "78") (name "Net-(OK2-EMIT)") (class "Default")
      (node (ref "OK2") (pin "3") (pinfunction "EMIT_3") (pintype "passive"))
      (node (ref "T11") (pin "B") (pinfunction "B_B") (pintype "passive"))
      (node (ref "T6") (pin "B") (pinfunction "B_B") (pintype "passive"))
    )
    (net (code "79") (name "Net-(PS1-+VO)") (class "Default")
      (node (ref "C12") (pin "1") (pinfunction "1_1") (pintype "passive"))
      (node (ref "C32") (pin "+") (pinfunction "+_+") (pintype "passive"))
      (node (ref "PS1") (pin "4") (pinfunction "+VO_4") (pintype "output"))
      (node (ref "U13") (pin "8") (pinfunction "VCC_8") (pintype "power_in"))
    )
    (net (code "80") (name "Net-(PS1-AC1)") (class "Default")
      (node (ref "B2") (pin "AC1") (pinfunction "AC1_AC1") (pintype "passive"))
      (node (ref "F8") (pin "1") (pinfunction "1_1") (pintype "passive"))
      (node (ref "PS1") (pin "1") (pinfunction "AC1_1") (pintype "input"))
    )
    (net (code "81") (name "Net-(PS1-AC2)") (class "Default")
      (node (ref "B2") (pin "AC2") (pinfunction "AC2_AC2") (pintype "passive"))
      (node (ref "PS1") (pin "2") (pinfunction "AC2_2") (pintype "input"))
      (node (ref "X12") (pin "1") (pinfunction "KL_1") (pintype "passive"))
    )
    (net (code "82") (name "Net-(Q1-PadG)") (class "Default")
      (node (ref "Q1") (pin "G") (pinfunction "G_G") (pintype "passive"))
      (node (ref "R5") (pin "1") (pinfunction "1_1") (pintype "passive"))
      (node (ref "R8") (pin "1") (pinfunction "1_1") (pintype "passive"))
    )
    (net (code "83") (name "Net-(Q2-PadG)") (class "Default")
      (node (ref "Q2") (pin "G") (pinfunction "G_G") (pintype "passive"))
      (node (ref "R7") (pin "1") (pinfunction "1_1") (pintype "passive"))
      (node (ref "R9") (pin "1") (pinfunction "1_1") (pintype "passive"))
    )
    (net (code "84") (name "Net-(Q3-PadG)") (class "Default")
      (node (ref "Q3") (pin "G") (pinfunction "G_G") (pintype "passive"))
      (node (ref "R10") (pin "1") (pinfunction "1_1") (pintype "passive"))
      (node (ref "R13") (pin "1") (pinfunction "1_1") (pintype "passive"))
    )
    (net (code "85") (name "Net-(Q4-PadG)") (class "Default")
      (node (ref "Q4") (pin "G") (pinfunction "G_G") (pintype "passive"))
      (node (ref "R27") (pin "2") (pinfunction "2_2") (pintype "passive"))
      (node (ref "R29") (pin "2") (pinfunction "2_2") (pintype "passive"))
    )
    (net (code "86") (name "Net-(Q5-PadG)") (class "Default")
      (node (ref "Q5") (pin "G") (pinfunction "G_G") (pintype "passive"))
      (node (ref "R25") (pin "1") (pinfunction "1_1") (pintype "passive"))
    )
    (net (code "87") (name "Net-(Q6-PadG)") (class "Default")
      (node (ref "Q6") (pin "G") (pinfunction "G_G") (pintype "passive"))
      (node (ref "R28") (pin "2") (pinfunction "2_2") (pintype "passive"))
      (node (ref "R32") (pin "2") (pinfunction "2_2") (pintype "passive"))
    )
    (net (code "88") (name "Net-(Q8-PadS)") (class "Default")
      (node (ref "Q8") (pin "S") (pinfunction "S_S") (pintype "passive"))
      (node (ref "Q9") (pin "D") (pinfunction "D_D") (pintype "passive"))
      (node (ref "U11") (pin "1") (pinfunction "IP+_1") (pintype "input"))
      (node (ref "U11") (pin "2") (pinfunction "IP+_2") (pintype "input"))
    )
    (net (code "89") (name "Net-(Q10-PadG)") (class "Default")
      (node (ref "Q10") (pin "G") (pinfunction "G_G") (pintype "passive"))
      (node (ref "R31") (pin "2") (pinfunction "2_2") (pintype "passive"))
    )
    (net (code "90") (name "Net-(Q11-PadG)") (class "Default")
      (node (ref "Q11") (pin "G") (pinfunction "G_G") (pintype "passive"))
      (node (ref "R56") (pin "2") (pinfunction "2_2") (pintype "passive"))
    )
    (net (code "91") (name "Net-(Q12-PadD)") (class "Default")
      (node (ref "Q12") (pin "D") (pinfunction "D_D") (pintype "passive"))
      (node (ref "Q16") (pin "D") (pinfunction "D_D") (pintype "passive"))
    )
    (net (code "92") (name "Net-(Q12-PadG)") (class "Default")
      (node (ref "Q12") (pin "G") (pinfunction "G_G") (pintype "passive"))
      (node (ref "R48") (pin "1") (pinfunction "1_1") (pintype "passive"))
      (node (ref "R52") (pin "2") (pinfunction "2_2") (pintype "passive"))
    )
    (net (code "93") (name "Net-(Q13-PadG)") (class "Default")
      (node (ref "Q13") (pin "G") (pinfunction "G_G") (pintype "passive"))
      (node (ref "R34") (pin "1") (pinfunction "1_1") (pintype "passive"))
    )
    (net (code "94") (name "Net-(Q15-PadG)") (class "Default")
      (node (ref "Q15") (pin "G") (pinfunction "G_G") (pintype "passive"))
      (node (ref "R37") (pin "1") (pinfunction "1_1") (pintype "passive"))
    )
    (net (code "95") (name "Net-(Q16-PadG)") (class "Default")
      (node (ref "Q16") (pin "G") (pinfunction "G_G") (pintype "passive"))
      (node (ref "R23") (pin "1") (pinfunction "1_1") (pintype "passive"))
      (node (ref "R53") (pin "1") (pinfunction "1_1") (pintype "passive"))
    )
    (net (code "96") (name "Net-(Q21-PadG)") (class "Default")
      (node (ref "Q21") (pin "G") (pinfunction "G_G") (pintype "passive"))
      (node (ref "R11") (pin "1") (pinfunction "1_1") (pintype "passive"))
      (node (ref "R15") (pin "1") (pinfunction "1_1") (pintype "passive"))
    )
    (net (code "97") (name "Net-(Q22-PadG)") (class "Default")
      (node (ref "Q22") (pin "G") (pinfunction "G_G") (pintype "passive"))
      (node (ref "R16") (pin "1") (pinfunction "1_1") (pintype "passive"))
      (node (ref "R6") (pin "1") (pinfunction "1_1") (pintype "passive"))
    )
    (net (code "98") (name "Net-(Q23-PadG)") (class "Default")
      (node (ref "Q23") (pin "G") (pinfunction "G_G") (pintype "passive"))
      (node (ref "R12") (pin "1") (pinfunction "1_1") (pintype "passive"))
      (node (ref "R14") (pin "1") (pinfunction "1_1") (pintype "passive"))
    )
    (net (code "99") (name "Net-(R24-Pad2)") (class "Default")
      (node (ref "R24") (pin "2") (pinfunction "2_2") (pintype "passive"))
      (node (ref "R25") (pin "2") (pinfunction "2_2") (pintype "passive"))
      (node (ref "T4") (pin "C") (pinfunction "C_C") (pintype "passive"))
    )
    (net (code "100") (name "Net-(R30-Pad1)") (class "Default")
      (node (ref "R30") (pin "1") (pinfunction "1_1") (pintype "passive"))
      (node (ref "R31") (pin "1") (pinfunction "1_1") (pintype "passive"))
      (node (ref "T6") (pin "C") (pinfunction "C_C") (pintype "passive"))
    )
    (net (code "101") (name "Net-(R39-Pad1)") (class "Default")
      (node (ref "R39") (pin "1") (pinfunction "1_1") (pintype "passive"))
      (node (ref "T7") (pin "C") (pinfunction "C_C") (pintype "passive"))
    )
    (net (code "102") (name "Net-(R40-Pad1)") (class "Default")
      (node (ref "R40") (pin "1") (pinfunction "1_1") (pintype "passive"))
      (node (ref "T8") (pin "C") (pinfunction "C_C") (pintype "passive"))
    )
    (net (code "103") (name "Net-(R55-Pad1)") (class "Default")
      (node (ref "R55") (pin "1") (pinfunction "1_1") (pintype "passive"))
      (node (ref "R56") (pin "1") (pinfunction "1_1") (pintype "passive"))
      (node (ref "T11") (pin "C") (pinfunction "C_C") (pintype "passive"))
    )
    (net (code "104") (name "Net-(R59-Pad1)") (class "Default")
      (node (ref "R59") (pin "1") (pinfunction "1_1") (pintype "passive"))
      (node (ref "T13") (pin "C") (pinfunction "C_C") (pintype "passive"))
    )
    (net (code "105") (name "Net-(R62-Pad1)") (class "Default")
      (node (ref "R62") (pin "1") (pinfunction "1_1") (pintype "passive"))
      (node (ref "T15") (pin "C") (pinfunction "C_C") (pintype "passive"))
    )
    (net (code "106") (name "Net-(T1-A1)") (class "Default")
      (node (ref "D3") (pin "C") (pinfunction "C_C") (pintype "passive"))
      (node (ref "D4") (pin "A") (pinfunction "A_A") (pintype "passive"))
      (node (ref "R36") (pin "1") (pinfunction "1_1") (pintype "passive"))
      (node (ref "T1") (pin "T1") (pinfunction "A1_T1") (pintype "passive"))
    )
    (net (code "107") (name "Net-(T3-A1)") (class "Default")
      (node (ref "D5") (pin "C") (pinfunction "C_C") (pintype "passive"))
      (node (ref "D6") (pin "A") (pinfunction "A_A") (pintype "passive"))
      (node (ref "R18") (pin "2") (pinfunction "2_2") (pintype "passive"))
      (node (ref "T3") (pin "T1") (pinfunction "A1_T1") (pintype "passive"))
    )
    (net (code "108") (name "Net-(T5-A1)") (class "Default")
      (node (ref "D14") (pin "A") (pinfunction "A_A") (pintype "passive"))
      (node (ref "R58") (pin "1") (pinfunction "1_1") (pintype "passive"))
      (node (ref "T5") (pin "T1") (pinfunction "A1_T1") (pintype "passive"))
    )
    (net (code "109") (name "Net-(T9-A1)") (class "Default")
      (node (ref "D16") (pin "A") (pinfunction "A_A") (pintype "passive"))
      (node (ref "R61") (pin "1") (pinfunction "1_1") (pintype "passive"))
      (node (ref "T9") (pin "T1") (pinfunction "A1_T1") (pintype "passive"))
    )
    (net (code "110") (name "Net-(U$4-L)") (class "Default")
      (node (ref "F4") (pin "2") (pinfunction "2_2") (pintype "passive"))
      (node (ref "R44") (pin "1") (pinfunction "1_1") (pintype "passive"))
      (node (ref "U$4") (pin "P1.1") (pinfunction "L_P1.1") (pintype "passive"))
      (node (ref "X6") (pin "3") (pinfunction "KL_3") (pintype "passive"))
      (node (ref "X6") (pin "4") (pinfunction "KL_4") (pintype "passive"))
    )
    (net (code "111") (name "Net-(U$4-N)") (class "Default")
      (node (ref "R43") (pin "1") (pinfunction "1_1") (pintype "passive"))
      (node (ref "U$4") (pin "P1.2") (pinfunction "N_P1.2") (pintype "passive"))
      (node (ref "U11") (pin "3") (pinfunction "IP-_3") (pintype "input"))
      (node (ref "U11") (pin "4") (pinfunction "IP-_4") (pintype "input"))
      (node (ref "X6") (pin "1") (pinfunction "KL_1") (pintype "passive"))
      (node (ref "X6") (pin "2") (pinfunction "KL_2") (pintype "passive"))
    )
    (net (code "112") (name "Net-(U$4-OUT)") (class "Default")
      (node (ref "R46") (pin "1") (pinfunction "1_1") (pintype "passive"))
      (node (ref "U$4") (pin "3") (pinfunction "OUT_3") (pintype "output"))
    )
    (net (code "113") (name "Net-(U2-A)") (class "Default")
      (node (ref "R3") (pin "1") (pinfunction "1_1") (pintype "passive"))
      (node (ref "U2") (pin "2") (pinfunction "A_2") (pintype "passive"))
    )
    (net (code "114") (name "Net-(U2-VCC)") (class "Default")
      (node (ref "C14") (pin "1") (pinfunction "1_1") (pintype "passive"))
      (node (ref "F5") (pin "1") (pinfunction "1_1") (pintype "passive"))
      (node (ref "U2") (pin "8") (pinfunction "VCC_8") (pintype "power_in"))
    )
    (net (code "115") (name "Net-(U2-VO1)") (class "Default")
      (node (ref "R19") (pin "2") (pinfunction "2_2") (pintype "passive"))
      (node (ref "U2") (pin "6") (pinfunction "VO1_6") (pintype "passive"))
      (node (ref "U2") (pin "7") (pinfunction "VO2_7") (pintype "passive"))
    )
    (net (code "116") (name "Net-(U3-A)") (class "Default")
      (node (ref "R4") (pin "1") (pinfunction "1_1") (pintype "passive"))
      (node (ref "U3") (pin "2") (pinfunction "A_2") (pintype "passive"))
    )
    (net (code "117") (name "Net-(U3-VCC)") (class "Default")
      (node (ref "C16") (pin "1") (pinfunction "1_1") (pintype "passive"))
      (node (ref "F6") (pin "1") (pinfunction "1_1") (pintype "passive"))
      (node (ref "U3") (pin "8") (pinfunction "VCC_8") (pintype "power_in"))
    )
    (net (code "118") (name "Net-(U3-VO1)") (class "Default")
      (node (ref "R20") (pin "2") (pinfunction "2_2") (pintype "passive"))
      (node (ref "U3") (pin "6") (pinfunction "VO1_6") (pintype "passive"))
      (node (ref "U3") (pin "7") (pinfunction "VO2_7") (pintype "passive"))
    )
    (net (code "119") (name "Net-(U4-CATHODE)") (class "Default")
      (node (ref "LED5") (pin "A") (pinfunction "A_A") (pintype "passive"))
      (node (ref "U4") (pin "2") (pinfunction "CATHODE_2") (pintype "passive"))
    )
    (net (code "120") (name "Net-(U4-MAIN_TERM1)") (class "Default")
      (node (ref "R35") (pin "1") (pinfunction "1_1") (pintype "passive"))
      (node (ref "U4") (pin "6") (pinfunction "MAIN_TERM1_6") (pintype "passive"))
    )
    (net (code "121") (name "Net-(U4-MAIN_TERM2)") (class "Default")
      (node (ref "R18") (pin "1") (pinfunction "1_1") (pintype "passive"))
      (node (ref "T3") (pin "G") (pinfunction "G_G") (pintype "passive"))
      (node (ref "U4") (pin "4") (pinfunction "MAIN_TERM2_4") (pintype "passive"))
    )
    (net (code "122") (name "Net-(U5-CATHODE)") (class "Default")
      (node (ref "LED6") (pin "A") (pinfunction "A_A") (pintype "passive"))
      (node (ref "U5") (pin "2") (pinfunction "CATHODE_2") (pintype "passive"))
    )
    (net (code "123") (name "Net-(U5-MAIN_TERM1)") (class "Default")
      (node (ref "R17") (pin "2") (pinfunction "2_2") (pintype "passive"))
      (node (ref "U5") (pin "6") (pinfunction "MAIN_TERM1_6") (pintype "passive"))
    )
    (net (code "124") (name "Net-(U5-MAIN_TERM2)") (class "Default")
      (node (ref "R36") (pin "2") (pinfunction "2_2") (pintype "passive"))
      (node (ref "T1") (pin "G") (pinfunction "G_G") (pintype "passive"))
      (node (ref "U5") (pin "4") (pinfunction "MAIN_TERM2_4") (pintype "passive"))
    )
    (net (code "125") (name "Net-(U6-HIN)") (class "Default")
      (node (ref "R38") (pin "1") (pinfunction "1_1") (pintype "passive"))
      (node (ref "U6") (pin "2") (pinfunction "HIN_2") (pintype "input"))
    )
    (net (code "126") (name "Net-(U6-HO)") (class "Default")
      (node (ref "R34") (pin "2") (pinfunction "2_2") (pintype "passive"))
      (node (ref "U6") (pin "7") (pinfunction "HO_7") (pintype "output"))
    )
    (net (code "127") (name "Net-(U6-LIN)") (class "Default")
      (node (ref "C19") (pin "1") (pinfunction "1_1") (pintype "passive"))
      (node (ref "R38") (pin "2") (pinfunction "2_2") (pintype "passive"))
      (node (ref "U6") (pin "3") (pinfunction "LIN_3") (pintype "input"))
    )
    (net (code "128") (name "Net-(U6-LO)") (class "Default")
      (node (ref "R37") (pin "2") (pinfunction "2_2") (pintype "passive"))
      (node (ref "U6") (pin "5") (pinfunction "LO_5") (pintype "output"))
    )
    (net (code "129") (name "Net-(U6-VB)") (class "Default")
      (node (ref "C20") (pin "+") (pinfunction "+_+") (pintype "passive"))
      (node (ref "D11") (pin "C") (pinfunction "C_C") (pintype "passive"))
      (node (ref "U6") (pin "8") (pinfunction "VB_8") (pintype "power_in"))
    )
    (net (code "130") (name "Net-(U6-VCC)") (class "Default")
      (node (ref "C22") (pin "+") (pinfunction "+_+") (pintype "passive"))
      (node (ref "D11") (pin "A") (pinfunction "A_A") (pintype "passive"))
      (node (ref "R45") (pin "2") (pinfunction "2_2") (pintype "passive"))
      (node (ref "U6") (pin "1") (pinfunction "VCC_1") (pintype "power_in"))
    )
    (net (code "131") (name "Net-(U6-VS)") (class "Default")
      (node (ref "C20") (pin "-") (pinfunction "-_-") (pintype "passive"))
      (node (ref "U6") (pin "6") (pinfunction "VS_6") (pintype "output"))
    )
    (net (code "132") (name "Net-(U7-A)") (class "Default")
      (node (ref "R21") (pin "2") (pinfunction "2_2") (pintype "passive"))
      (node (ref "U7") (pin "2") (pinfunction "A_2") (pintype "passive"))
    )
    (net (code "133") (name "Net-(U7-VO1)") (class "Default")
      (node (ref "Q20") (pin "G") (pinfunction "G_G") (pintype "passive"))
      (node (ref "U7") (pin "6") (pinfunction "VO1_6") (pintype "passive"))
      (node (ref "U7") (pin "7") (pinfunction "VO2_7") (pintype "passive"))
    )
    (net (code "134") (name "Net-(U8-CATHODE)") (class "Default")
      (node (ref "LED9") (pin "A") (pinfunction "A_A") (pintype "passive"))
      (node (ref "U8") (pin "2") (pinfunction "CATHODE_2") (pintype "passive"))
    )
    (net (code "135") (name "Net-(U8-MAIN_TERM1)") (class "Default")
      (node (ref "R57") (pin "2") (pinfunction "2_2") (pintype "passive"))
      (node (ref "U8") (pin "6") (pinfunction "MAIN_TERM1_6") (pintype "passive"))
    )
    (net (code "136") (name "Net-(U8-MAIN_TERM2)") (class "Default")
      (node (ref "R58") (pin "2") (pinfunction "2_2") (pintype "passive"))
      (node (ref "T5") (pin "G") (pinfunction "G_G") (pintype "passive"))
      (node (ref "U8") (pin "4") (pinfunction "MAIN_TERM2_4") (pintype "passive"))
    )
    (net (code "137") (name "Net-(U9-HO)") (class "Default")
      (node (ref "F2") (pin "2") (pinfunction "2_2") (pintype "passive"))
      (node (ref "U9") (pin "7") (pinfunction "HO_7") (pintype "output"))
    )
    (net (code "138") (name "Net-(U9-LO)") (class "Default")
      (node (ref "F3") (pin "2") (pinfunction "2_2") (pintype "passive"))
      (node (ref "U9") (pin "5") (pinfunction "LO_5") (pintype "output"))
    )
    (net (code "139") (name "Net-(U10-CATHODE)") (class "Default")
      (node (ref "LED10") (pin "A") (pinfunction "A_A") (pintype "passive"))
      (node (ref "U10") (pin "2") (pinfunction "CATHODE_2") (pintype "passive"))
    )
    (net (code "140") (name "Net-(U10-MAIN_TERM1)") (class "Default")
      (node (ref "R60") (pin "2") (pinfunction "2_2") (pintype "passive"))
      (node (ref "U10") (pin "6") (pinfunction "MAIN_TERM1_6") (pintype "passive"))
    )
    (net (code "141") (name "Net-(U10-MAIN_TERM2)") (class "Default")
      (node (ref "R61") (pin "2") (pinfunction "2_2") (pintype "passive"))
      (node (ref "T9") (pin "G") (pinfunction "G_G") (pintype "passive"))
      (node (ref "U10") (pin "4") (pinfunction "MAIN_TERM2_4") (pintype "passive"))
    )
    (net (code "142") (name "Net-(U11-FILTER)") (class "Default")
      (node (ref "C30") (pin "1") (pinfunction "1_1") (pintype "passive"))
      (node (ref "U11") (pin "6") (pinfunction "FILTER_6") (pintype "passive"))
    )
    (net (code "143") (name "Net-(U12-FILTER)") (class "Default")
      (node (ref "C34") (pin "1") (pinfunction "1_1") (pintype "passive"))
      (node (ref "U12") (pin "6") (pinfunction "FILTER_6") (pintype "passive"))
    )
    (net (code "144") (name "Net-(U13-A)") (class "Default")
      (node (ref "R26") (pin "2") (pinfunction "2_2") (pintype "passive"))
      (node (ref "U13") (pin "2") (pinfunction "A_2") (pintype "passive"))
    )
    (net (code "145") (name "Net-(U14-RXD0)") (class "Default")
      (node (ref "U14") (pin "24") (pinfunction "RXD0_24") (pintype "input"))
      (node (ref "X1") (pin "3") (pinfunction "S_3") (pintype "passive"))
    )
    (net (code "146") (name "Net-(U14-TXD0)") (class "Default")
      (node (ref "U14") (pin "23") (pinfunction "TXD0_23") (pintype "output"))
      (node (ref "X1") (pin "2") (pinfunction "S_2") (pintype "passive"))
    )
    (net (code "147") (name "Net-(X8-KL)") (class "Default")
      (node (ref "F8") (pin "2") (pinfunction "2_2") (pintype "passive"))
      (node (ref "X8") (pin "1") (pinfunction "KL_1") (pintype "passive"))
    )
    (net (code "148") (name "unconnected-(U$3-3.3V-PadP$23)") (class "Default")
      (node (ref "U$3") (pin "P$23") (pinfunction "3.3V_P$23") (pintype "bidirectional"))
    )
    (net (code "149") (name "unconnected-(U$3-3.3V1-PadP$20)") (class "Default")
      (node (ref "U$3") (pin "P$20") (pinfunction "3.3V1_P$20") (pintype "bidirectional"))
    )
    (net (code "150") (name "unconnected-(U$3-PA5-PadP$31)") (class "Default")
      (node (ref "U$3") (pin "P$31") (pinfunction "PA5_P$31") (pintype "bidirectional"))
    )
    (net (code "151") (name "unconnected-(U$3-PA7-PadP$29)") (class "Default")
      (node (ref "U$3") (pin "P$29") (pinfunction "PA7_P$29") (pintype "bidirectional"))
    )
    (net (code "152") (name "unconnected-(U$3-PA10-PadP$7)") (class "Default")
      (node (ref "U$3") (pin "P$7") (pinfunction "PA10_P$7") (pintype "bidirectional"))
    )
    (net (code "153") (name "unconnected-(U$3-PA11-PadP$8)") (class "Default")
      (node (ref "U$3") (pin "P$8") (pinfunction "PA11_P$8") (pintype "bidirectional"))
    )
    (net (code "154") (name "unconnected-(U$3-PA12-PadP$9)") (class "Default")
      (node (ref "U$3") (pin "P$9") (pinfunction "PA12_P$9") (pintype "bidirectional"))
    )
    (net (code "155") (name "unconnected-(U$3-PA15-PadP$10)") (class "Default")
      (node (ref "U$3") (pin "P$10") (pinfunction "PA15_P$10") (pintype "bidirectional"))
    )
    (net (code "156") (name "unconnected-(U$3-PB7-PadP$15)") (class "Default")
      (node (ref "U$3") (pin "P$15") (pinfunction "PB7_P$15") (pintype "bidirectional"))
    )
    (net (code "157") (name "unconnected-(U$3-PB8-PadP$16)") (class "Default")
      (node (ref "U$3") (pin "P$16") (pinfunction "PB8_P$16") (pintype "bidirectional"))
    )
    (net (code "158") (name "unconnected-(U$3-PB9-PadP$17)") (class "Default")
      (node (ref "U$3") (pin "P$17") (pinfunction "PB9_P$17") (pintype "bidirectional"))
    )
    (net (code "159") (name "unconnected-(U$3-PB10-PadP$26)") (class "Default")
      (node (ref "U$3") (pin "P$26") (pinfunction "PB10_P$26") (pintype "bidirectional"))
    )
    (net (code "160") (name "unconnected-(U$3-PB11-PadP$25)") (class "Default")
      (node (ref "U$3") (pin "P$25") (pinfunction "PB11_P$25") (pintype "bidirectional"))
    )
    (net (code "161") (name "unconnected-(U$3-PB12-PadP$1)") (class "Default")
      (node (ref "U$3") (pin "P$1") (pinfunction "PB12_P$1") (pintype "bidirectional"))
    )
    (net (code "162") (name "unconnected-(U$3-PB13-PadP$2)") (class "Default")
      (node (ref "U$3") (pin "P$2") (pinfunction "PB13_P$2") (pintype "bidirectional"))
    )
    (net (code "163") (name "unconnected-(U$3-PB14-PadP$3)") (class "Default")
      (node (ref "U$3") (pin "P$3") (pinfunction "PB14_P$3") (pintype "bidirectional"))
    )
    (net (code "164") (name "unconnected-(U$3-PB15-PadP$4)") (class "Default")
      (node (ref "U$3") (pin "P$4") (pinfunction "PB15_P$4") (pintype "bidirectional"))
    )
    (net (code "165") (name "unconnected-(U$3-PC13-PadP$39)") (class "Default")
      (node (ref "U$3") (pin "P$39") (pinfunction "PC13_P$39") (pintype "bidirectional"))
    )
    (net (code "166") (name "unconnected-(U$3-PC14-PadP$38)") (class "Default")
      (node (ref "U$3") (pin "P$38") (pinfunction "PC14_P$38") (pintype "bidirectional"))
    )
    (net (code "167") (name "unconnected-(U$3-PC15-PadP$37)") (class "Default")
      (node (ref "U$3") (pin "P$37") (pinfunction "PC15_P$37") (pintype "bidirectional"))
    )
    (net (code "168") (name "unconnected-(U$3-RESET-PadP$24)") (class "Default")
      (node (ref "U$3") (pin "P$24") (pinfunction "RESET_P$24") (pintype "bidirectional"))
    )
    (net (code "169") (name "unconnected-(U$3-VBAT-PadP$40)") (class "Default")
      (node (ref "U$3") (pin "P$40") (pinfunction "VBAT_P$40") (pintype "bidirectional"))
    )
    (net (code "170") (name "unconnected-(U14-CLK-Pad38)") (class "Default")
      (node (ref "U14") (pin "38") (pinfunction "CLK_38") (pintype "input"))
    )
    (net (code "171") (name "unconnected-(U14-CMD-Pad18)") (class "Default")
      (node (ref "U14") (pin "18") (pinfunction "CMD_18") (pintype "bidirectional"))
    )
    (net (code "172") (name "unconnected-(U14-EN-Pad2)") (class "Default")
      (node (ref "U14") (pin "2") (pinfunction "EN_2") (pintype "input"))
    )
    (net (code "173") (name "unconnected-(U14-IO0-Pad33)") (class "Default")
      (node (ref "U14") (pin "33") (pinfunction "IO0_33") (pintype "bidirectional"))
    )
    (net (code "174") (name "unconnected-(U14-IO2-Pad34)") (class "Default")
      (node (ref "U14") (pin "34") (pinfunction "IO2_34") (pintype "bidirectional"))
    )
    (net (code "175") (name "unconnected-(U14-IO5-Pad29)") (class "Default")
      (node (ref "U14") (pin "29") (pinfunction "IO5_29") (pintype "bidirectional"))
    )
    (net (code "176") (name "unconnected-(U14-IO12-Pad13)") (class "Default")
      (node (ref "U14") (pin "13") (pinfunction "IO12_13") (pintype "bidirectional"))
    )
    (net (code "177") (name "unconnected-(U14-IO15-Pad35)") (class "Default")
      (node (ref "U14") (pin "35") (pinfunction "IO15_35") (pintype "bidirectional"))
    )
    (net (code "178") (name "unconnected-(U14-IO16-Pad31)") (class "Default")
      (node (ref "U14") (pin "31") (pinfunction "IO16_31") (pintype "bidirectional"))
    )
    (net (code "179") (name "unconnected-(U14-IO17-Pad30)") (class "Default")
      (node (ref "U14") (pin "30") (pinfunction "IO17_30") (pintype "bidirectional"))
    )
    (net (code "180") (name "unconnected-(U14-IO18-Pad28)") (class "Default")
      (node (ref "U14") (pin "28") (pinfunction "IO18_28") (pintype "bidirectional"))
    )
    (net (code "181") (name "unconnected-(U14-IO19-Pad27)") (class "Default")
      (node (ref "U14") (pin "27") (pinfunction "IO19_27") (pintype "bidirectional"))
    )
    (net (code "182") (name "unconnected-(U14-IO21-Pad25)") (class "Default")
      (node (ref "U14") (pin "25") (pinfunction "IO21_25") (pintype "bidirectional"))
    )
    (net (code "183") (name "unconnected-(U14-IO22-Pad22)") (class "Default")
      (node (ref "U14") (pin "22") (pinfunction "IO22_22") (pintype "bidirectional"))
    )
    (net (code "184") (name "unconnected-(U14-IO23-Pad21)") (class "Default")
      (node (ref "U14") (pin "21") (pinfunction "IO23_21") (pintype "bidirectional"))
    )
    (net (code "185") (name "unconnected-(U14-SD0-Pad37)") (class "Default")
      (node (ref "U14") (pin "37") (pinfunction "SD0_37") (pintype "bidirectional"))
    )
    (net (code "186") (name "unconnected-(U14-SD1-Pad36)") (class "Default")
      (node (ref "U14") (pin "36") (pinfunction "SD1_36") (pintype "bidirectional"))
    )
    (net (code "187") (name "unconnected-(U14-SD2-Pad16)") (class "Default")
      (node (ref "U14") (pin "16") (pinfunction "SD2_16") (pintype "bidirectional"))
    )
    (net (code "188") (name "unconnected-(U14-SD3-Pad17)") (class "Default")
      (node (ref "U14") (pin "17") (pinfunction "SD3_17") (pintype "bidirectional"))
    )
    (net (code "189") (name "unconnected-(U14-SENSOR_VN-Pad4)") (class "Default")
      (node (ref "U14") (pin "4") (pinfunction "SENSOR_VN_4") (pintype "input"))
    )
    (net (code "190") (name "unconnected-(U14-SENSOR_VP-Pad3)") (class "Default")
      (node (ref "U14") (pin "3") (pinfunction "SENSOR_VP_3") (pintype "input"))
    )
    (net (code "191") (name "unconnected-(X2C-KL-Pad3)") (class "Default")
      (node (ref "X2") (pin "3") (pinfunction "KL_3") (pintype "passive"))
    )
    (net (code "192") (name "unconnected-(X2G-KL-Pad7)") (class "Default")
      (node (ref "X2") (pin "7") (pinfunction "KL_7") (pintype "passive"))
    )
    (net (code "193") (name "unconnected-(X5C-KL-Pad3)") (class "Default")
      (node (ref "X5") (pin "3") (pinfunction "KL_3") (pintype "passive"))
    )
    (net (code "194") (name "unconnected-(X5D-KL-Pad4)") (class "Default")
      (node (ref "X5") (pin "4") (pinfunction "KL_4") (pintype "passive"))
    )
    (net (code "195") (name "unconnected-(X5E-KL-Pad5)") (class "Default")
      (node (ref "X5") (pin "5") (pinfunction "KL_5") (pintype "passive"))
    )
    (net (code "196") (name "unconnected-(X5F-KL-Pad6)") (class "Default")
      (node (ref "X5") (pin "6") (pinfunction "KL_6") (pintype "passive"))
    )
    (net (code "197") (name "unconnected-(X5G-KL-Pad7)") (class "Default")
      (node (ref "X5") (pin "7") (pinfunction "KL_7") (pintype "passive"))
    )
  )
)
